# ELC102_-_Switch_Interface.net
KiCad netlist of a schematic drawn in Altium Designer
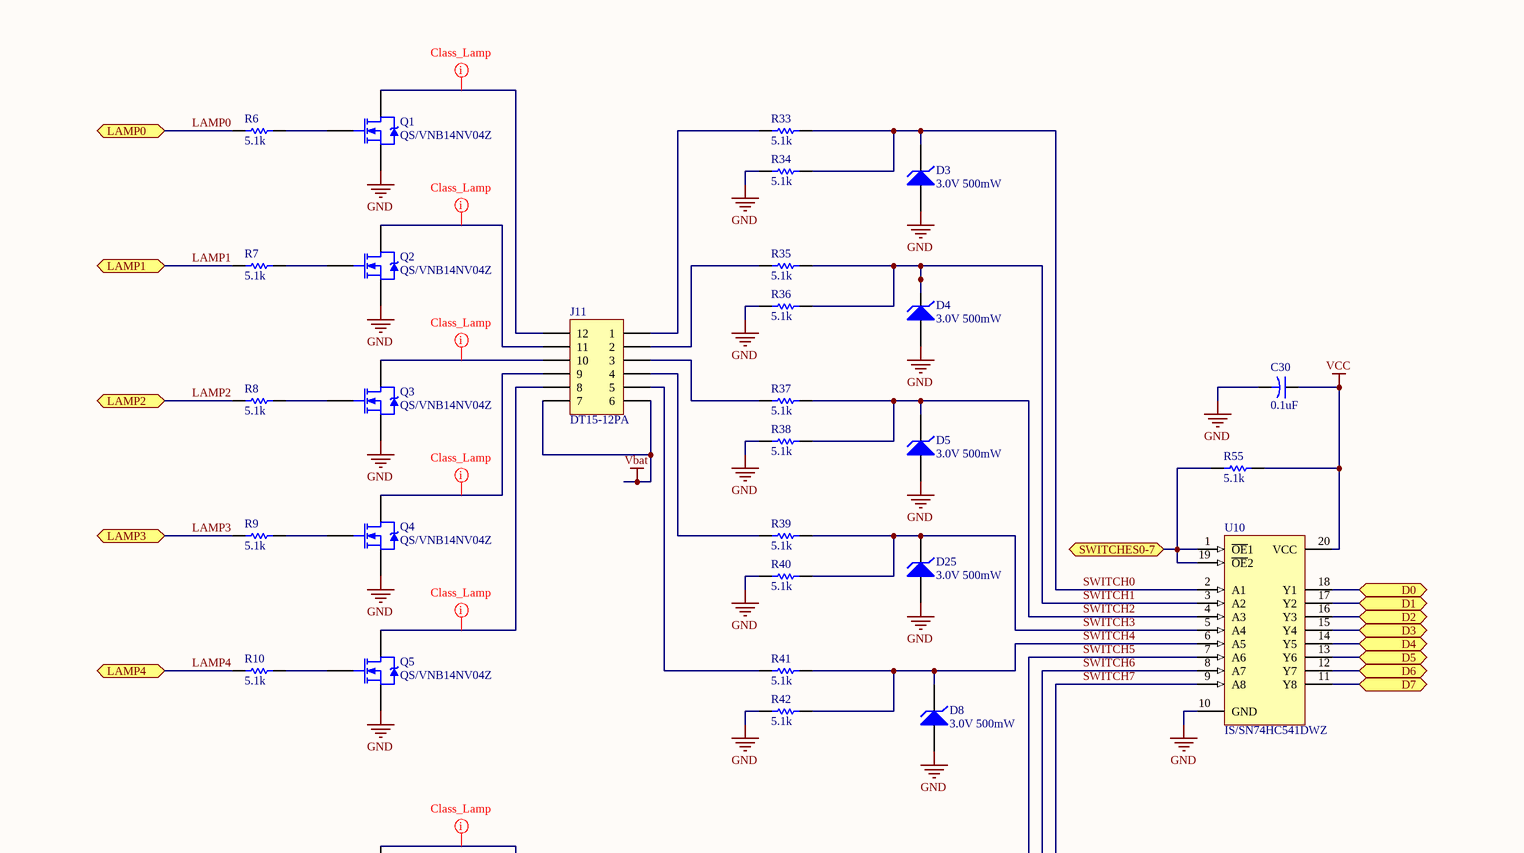
[diagram p0: ELC102 - Switch Interface.SchDoc, top left]
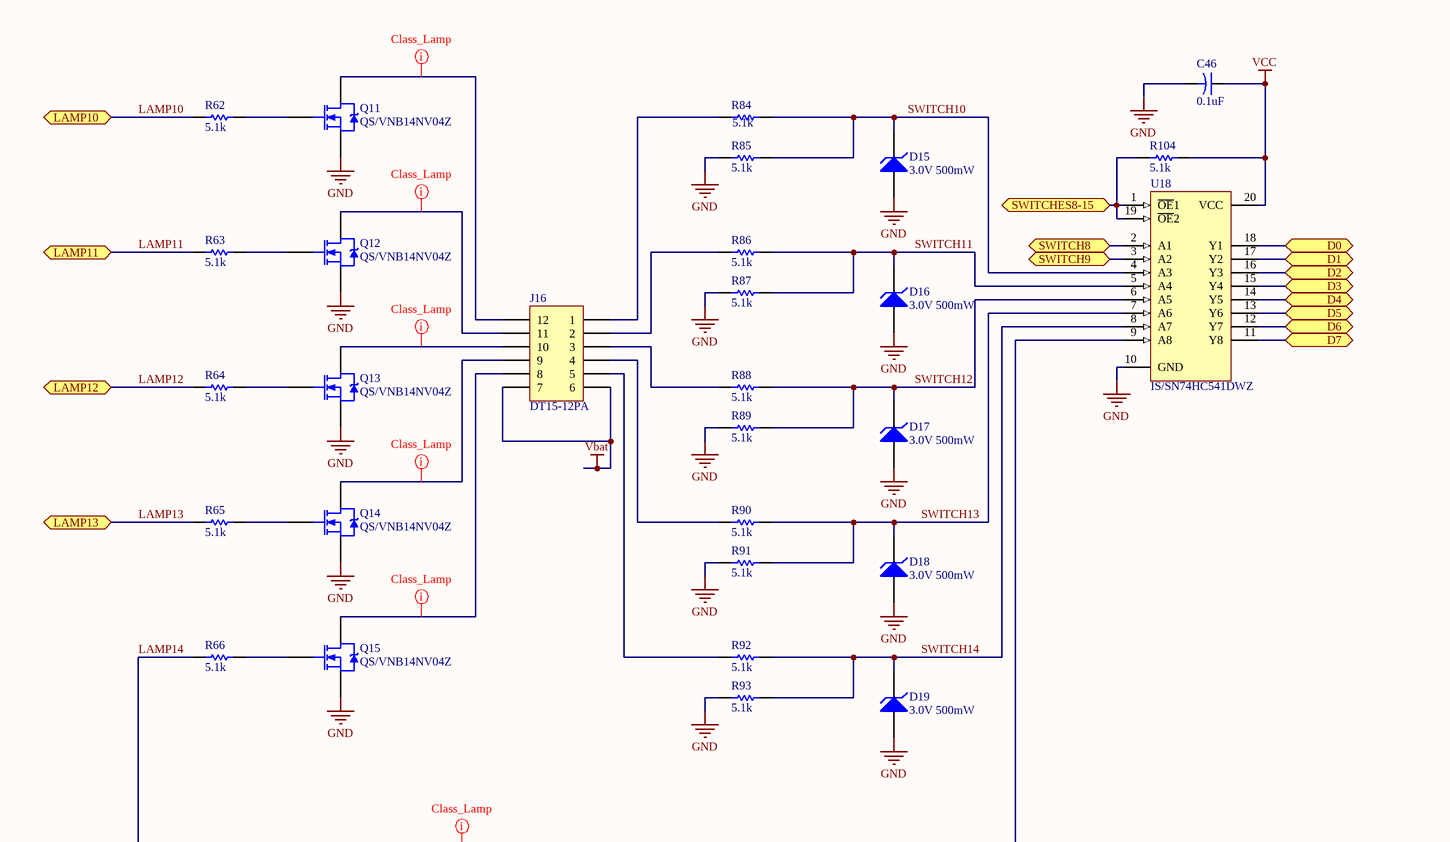
[diagram p1: ELC102 - Switch Interface.SchDoc, top right]
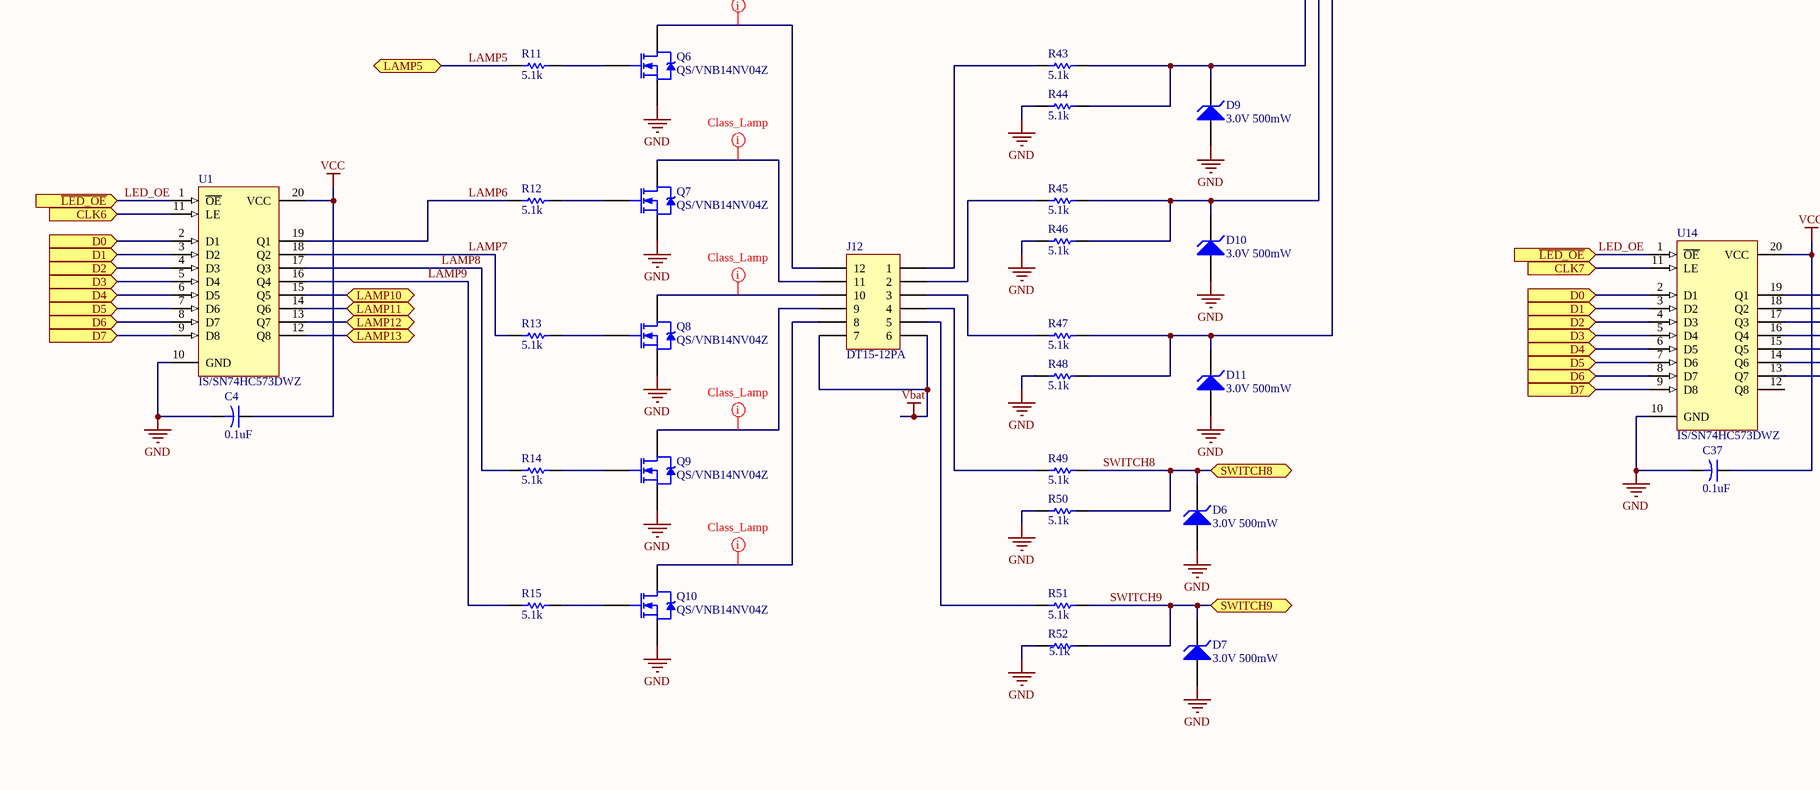
[diagram p2: ELC102 - Switch Interface.SchDoc, bottom left]
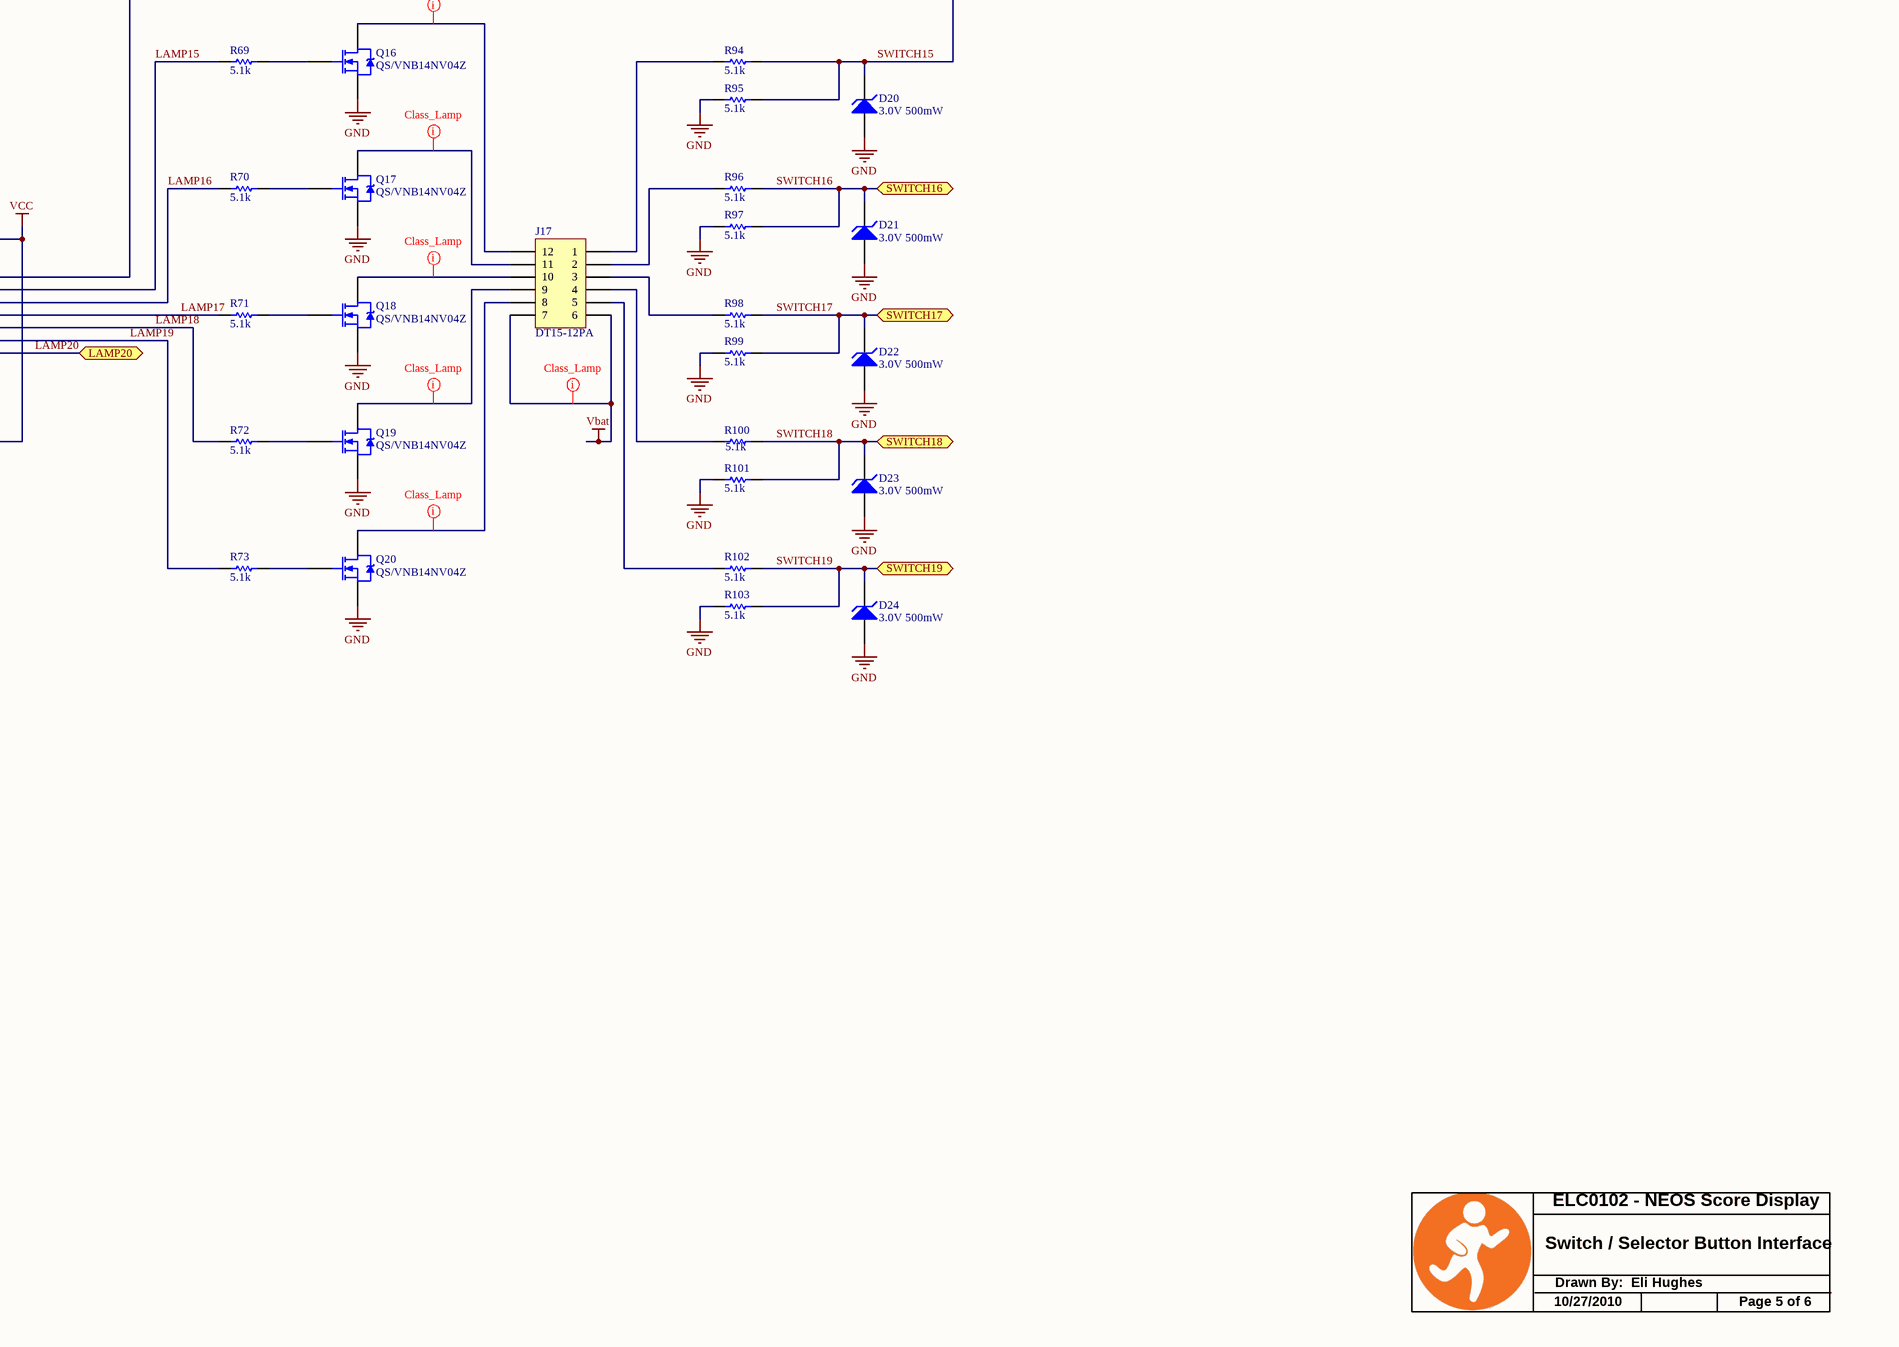
[diagram p3: ELC102 - Switch Interface.SchDoc, bottom right]

(export (version "E")
  (design (tool "Eeschema 10.0.6"))
  (components
    (comp (ref "C4")
      (value "0.1uF")
      (footprint "C0805")
      (description "Kemet .1uF 0805")
      (fields
        (field (name "MANUFACTURER") "Kemet")
        (field (name "MANUFACTURER PART NUMBER") "C0805C104K5RACTU")
        (field (name "SOURCE") "Digikey")
      )
      (libsource (lib "ScoreBoard") (part "CS/C0805C104K5RACK"))
    )
    (comp (ref "C30")
      (value "0.1uF")
      (footprint "C0805")
      (description "Kemet .1uF 0805")
      (fields
        (field (name "MANUFACTURER") "Kemet")
        (field (name "MANUFACTURER PART NUMBER") "C0805C104K5RACTU")
        (field (name "SOURCE") "Digikey")
      )
      (libsource (lib "ScoreBoard") (part "CS/C0805C104K5RACK"))
    )
    (comp (ref "C37")
      (value "0.1uF")
      (footprint "C0805")
      (description "Kemet .1uF 0805")
      (fields
        (field (name "MANUFACTURER") "Kemet")
        (field (name "MANUFACTURER PART NUMBER") "C0805C104K5RACTU")
        (field (name "SOURCE") "Digikey")
      )
      (libsource (lib "ScoreBoard") (part "CS/C0805C104K5RACK"))
    )
    (comp (ref "C46")
      (value "0.1uF")
      (footprint "C0805")
      (description "Kemet .1uF 0805")
      (fields
        (field (name "MANUFACTURER") "Kemet")
        (field (name "MANUFACTURER PART NUMBER") "C0805C104K5RACTU")
        (field (name "SOURCE") "Digikey")
      )
      (libsource (lib "ScoreBoard") (part "CS/C0805C104K5RACK"))
    )
    (comp (ref "D3")
      (value "3.0V 500mW")
      (footprint "SOD123")
      (description "Zener 3.0V SOD-123")
      (fields
        (field (name "MANUFACTURER") "ON Semiconductor")
        (field (name "MANUFACTURER PART NUMBER") "MMSZ5225BT1G")
        (field (name "SOURCE") "Digikey")
      )
      (libsource (lib "ScoreBoard") (part "DS/MMSZ5225BT1Z"))
    )
    (comp (ref "D4")
      (value "3.0V 500mW")
      (footprint "SOD123")
      (description "Zener 3.0V SOD-123")
      (fields
        (field (name "MANUFACTURER") "ON Semiconductor")
        (field (name "MANUFACTURER PART NUMBER") "MMSZ5225BT1G")
        (field (name "SOURCE") "Digikey")
      )
      (libsource (lib "ScoreBoard") (part "DS/MMSZ5225BT1Z"))
    )
    (comp (ref "D5")
      (value "3.0V 500mW")
      (footprint "SOD123")
      (description "Zener 3.0V SOD-123")
      (fields
        (field (name "MANUFACTURER") "ON Semiconductor")
        (field (name "MANUFACTURER PART NUMBER") "MMSZ5225BT1G")
        (field (name "SOURCE") "Digikey")
      )
      (libsource (lib "ScoreBoard") (part "DS/MMSZ5225BT1Z"))
    )
    (comp (ref "D6")
      (value "3.0V 500mW")
      (footprint "SOD123")
      (description "Zener 3.0V SOD-123")
      (fields
        (field (name "MANUFACTURER") "ON Semiconductor")
        (field (name "MANUFACTURER PART NUMBER") "MMSZ5225BT1G")
        (field (name "SOURCE") "Digikey")
      )
      (libsource (lib "ScoreBoard") (part "DS/MMSZ5225BT1Z"))
    )
    (comp (ref "D7")
      (value "3.0V 500mW")
      (footprint "SOD123")
      (description "Zener 3.0V SOD-123")
      (fields
        (field (name "MANUFACTURER") "ON Semiconductor")
        (field (name "MANUFACTURER PART NUMBER") "MMSZ5225BT1G")
        (field (name "SOURCE") "Digikey")
      )
      (libsource (lib "ScoreBoard") (part "DS/MMSZ5225BT1Z"))
    )
    (comp (ref "D8")
      (value "3.0V 500mW")
      (footprint "SOD123")
      (description "Zener 3.0V SOD-123")
      (fields
        (field (name "MANUFACTURER") "ON Semiconductor")
        (field (name "MANUFACTURER PART NUMBER") "MMSZ5225BT1G")
        (field (name "SOURCE") "Digikey")
      )
      (libsource (lib "ScoreBoard") (part "DS/MMSZ5225BT1Z"))
    )
    (comp (ref "D9")
      (value "3.0V 500mW")
      (footprint "SOD123")
      (description "Zener 3.0V SOD-123")
      (fields
        (field (name "MANUFACTURER") "ON Semiconductor")
        (field (name "MANUFACTURER PART NUMBER") "MMSZ5225BT1G")
        (field (name "SOURCE") "Digikey")
      )
      (libsource (lib "ScoreBoard") (part "DS/MMSZ5225BT1Z"))
    )
    (comp (ref "D10")
      (value "3.0V 500mW")
      (footprint "SOD123")
      (description "Zener 3.0V SOD-123")
      (fields
        (field (name "MANUFACTURER") "ON Semiconductor")
        (field (name "MANUFACTURER PART NUMBER") "MMSZ5225BT1G")
        (field (name "SOURCE") "Digikey")
      )
      (libsource (lib "ScoreBoard") (part "DS/MMSZ5225BT1Z"))
    )
    (comp (ref "D11")
      (value "3.0V 500mW")
      (footprint "SOD123")
      (description "Zener 3.0V SOD-123")
      (fields
        (field (name "MANUFACTURER") "ON Semiconductor")
        (field (name "MANUFACTURER PART NUMBER") "MMSZ5225BT1G")
        (field (name "SOURCE") "Digikey")
      )
      (libsource (lib "ScoreBoard") (part "DS/MMSZ5225BT1Z"))
    )
    (comp (ref "D15")
      (value "3.0V 500mW")
      (footprint "SOD123")
      (description "Zener 3.0V SOD-123")
      (fields
        (field (name "MANUFACTURER") "ON Semiconductor")
        (field (name "MANUFACTURER PART NUMBER") "MMSZ5225BT1G")
        (field (name "SOURCE") "Digikey")
      )
      (libsource (lib "ScoreBoard") (part "DS/MMSZ5225BT1Z"))
    )
    (comp (ref "D16")
      (value "3.0V 500mW")
      (footprint "SOD123")
      (description "Zener 3.0V SOD-123")
      (fields
        (field (name "MANUFACTURER") "ON Semiconductor")
        (field (name "MANUFACTURER PART NUMBER") "MMSZ5225BT1G")
        (field (name "SOURCE") "Digikey")
      )
      (libsource (lib "ScoreBoard") (part "DS/MMSZ5225BT1Z"))
    )
    (comp (ref "D17")
      (value "3.0V 500mW")
      (footprint "SOD123")
      (description "Zener 3.0V SOD-123")
      (fields
        (field (name "MANUFACTURER") "ON Semiconductor")
        (field (name "MANUFACTURER PART NUMBER") "MMSZ5225BT1G")
        (field (name "SOURCE") "Digikey")
      )
      (libsource (lib "ScoreBoard") (part "DS/MMSZ5225BT1Z"))
    )
    (comp (ref "D18")
      (value "3.0V 500mW")
      (footprint "SOD123")
      (description "Zener 3.0V SOD-123")
      (fields
        (field (name "MANUFACTURER") "ON Semiconductor")
        (field (name "MANUFACTURER PART NUMBER") "MMSZ5225BT1G")
        (field (name "SOURCE") "Digikey")
      )
      (libsource (lib "ScoreBoard") (part "DS/MMSZ5225BT1Z"))
    )
    (comp (ref "D19")
      (value "3.0V 500mW")
      (footprint "SOD123")
      (description "Zener 3.0V SOD-123")
      (fields
        (field (name "MANUFACTURER") "ON Semiconductor")
        (field (name "MANUFACTURER PART NUMBER") "MMSZ5225BT1G")
        (field (name "SOURCE") "Digikey")
      )
      (libsource (lib "ScoreBoard") (part "DS/MMSZ5225BT1Z"))
    )
    (comp (ref "D20")
      (value "3.0V 500mW")
      (footprint "SOD123")
      (description "Zener 3.0V SOD-123")
      (fields
        (field (name "MANUFACTURER") "ON Semiconductor")
        (field (name "MANUFACTURER PART NUMBER") "MMSZ5225BT1G")
        (field (name "SOURCE") "Digikey")
      )
      (libsource (lib "ScoreBoard") (part "DS/MMSZ5225BT1Z"))
    )
    (comp (ref "D21")
      (value "3.0V 500mW")
      (footprint "SOD123")
      (description "Zener 3.0V SOD-123")
      (fields
        (field (name "MANUFACTURER") "ON Semiconductor")
        (field (name "MANUFACTURER PART NUMBER") "MMSZ5225BT1G")
        (field (name "SOURCE") "Digikey")
      )
      (libsource (lib "ScoreBoard") (part "DS/MMSZ5225BT1Z"))
    )
    (comp (ref "D22")
      (value "3.0V 500mW")
      (footprint "SOD123")
      (description "Zener 3.0V SOD-123")
      (fields
        (field (name "MANUFACTURER") "ON Semiconductor")
        (field (name "MANUFACTURER PART NUMBER") "MMSZ5225BT1G")
        (field (name "SOURCE") "Digikey")
      )
      (libsource (lib "ScoreBoard") (part "DS/MMSZ5225BT1Z"))
    )
    (comp (ref "D23")
      (value "3.0V 500mW")
      (footprint "SOD123")
      (description "Zener 3.0V SOD-123")
      (fields
        (field (name "MANUFACTURER") "ON Semiconductor")
        (field (name "MANUFACTURER PART NUMBER") "MMSZ5225BT1G")
        (field (name "SOURCE") "Digikey")
      )
      (libsource (lib "ScoreBoard") (part "DS/MMSZ5225BT1Z"))
    )
    (comp (ref "D24")
      (value "3.0V 500mW")
      (footprint "SOD123")
      (description "Zener 3.0V SOD-123")
      (fields
        (field (name "MANUFACTURER") "ON Semiconductor")
        (field (name "MANUFACTURER PART NUMBER") "MMSZ5225BT1G")
        (field (name "SOURCE") "Digikey")
      )
      (libsource (lib "ScoreBoard") (part "DS/MMSZ5225BT1Z"))
    )
    (comp (ref "D25")
      (value "3.0V 500mW")
      (footprint "SOD123")
      (description "Zener 3.0V SOD-123")
      (fields
        (field (name "MANUFACTURER") "ON Semiconductor")
        (field (name "MANUFACTURER PART NUMBER") "MMSZ5225BT1G")
        (field (name "SOURCE") "Digikey")
      )
      (libsource (lib "ScoreBoard") (part "DS/MMSZ5225BT1Z"))
    )
    (comp (ref "J11")
      (value "DT15-12PA")
      (footprint "JDT1512PA00Z")
      (description "Deutsch 12P Sealed PCB connector")
      (fields (field (name "MANUFACTURER") "Deutsch"))
      (libsource (lib "ScoreBoard") (part "JDT1512PA00Z"))
    )
    (comp (ref "J12")
      (value "DT15-12PA")
      (footprint "JDT1512PA00Z")
      (description "Deutsch 12P Sealed PCB connector")
      (fields (field (name "MANUFACTURER") "Deutsch"))
      (libsource (lib "ScoreBoard") (part "JDT1512PA00Z"))
    )
    (comp (ref "J16")
      (value "DT15-12PA")
      (footprint "JDT1512PA00Z")
      (description "Deutsch 12P Sealed PCB connector")
      (fields (field (name "MANUFACTURER") "Deutsch"))
      (libsource (lib "ScoreBoard") (part "JDT1512PA00Z"))
    )
    (comp (ref "J17")
      (value "DT15-12PA")
      (footprint "JDT1512PA00Z")
      (description "Deutsch 12P Sealed PCB connector")
      (fields (field (name "MANUFACTURER") "Deutsch"))
      (libsource (lib "ScoreBoard") (part "JDT1512PA00Z"))
    )
    (comp (ref "Q1")
      (value "QS/VNB14NV04Z")
      (footprint "D2PAK")
      (description "HEXFET Power MOSFET")
      (fields
        (field (name "MANUFACTURER") "STMicroelectronics")
        (field (name "MANUFACTURER PART NUMBER") "VNB14NV04")
        (field (name "SOURCE") "Digikey")
      )
      (libsource (lib "ScoreBoard") (part "QS/VNB14NV04Z"))
    )
    (comp (ref "Q2")
      (value "QS/VNB14NV04Z")
      (footprint "D2PAK")
      (description "HEXFET Power MOSFET")
      (fields
        (field (name "MANUFACTURER") "STMicroelectronics")
        (field (name "MANUFACTURER PART NUMBER") "VNB14NV04")
        (field (name "SOURCE") "Digikey")
      )
      (libsource (lib "ScoreBoard") (part "QS/VNB14NV04Z"))
    )
    (comp (ref "Q3")
      (value "QS/VNB14NV04Z")
      (footprint "D2PAK")
      (description "HEXFET Power MOSFET")
      (fields
        (field (name "MANUFACTURER") "STMicroelectronics")
        (field (name "MANUFACTURER PART NUMBER") "VNB14NV04")
        (field (name "SOURCE") "Digikey")
      )
      (libsource (lib "ScoreBoard") (part "QS/VNB14NV04Z"))
    )
    (comp (ref "Q4")
      (value "QS/VNB14NV04Z")
      (footprint "D2PAK")
      (description "HEXFET Power MOSFET")
      (fields
        (field (name "MANUFACTURER") "STMicroelectronics")
        (field (name "MANUFACTURER PART NUMBER") "VNB14NV04")
        (field (name "SOURCE") "Digikey")
      )
      (libsource (lib "ScoreBoard") (part "QS/VNB14NV04Z"))
    )
    (comp (ref "Q5")
      (value "QS/VNB14NV04Z")
      (footprint "D2PAK")
      (description "HEXFET Power MOSFET")
      (fields
        (field (name "MANUFACTURER") "STMicroelectronics")
        (field (name "MANUFACTURER PART NUMBER") "VNB14NV04")
        (field (name "SOURCE") "Digikey")
      )
      (libsource (lib "ScoreBoard") (part "QS/VNB14NV04Z"))
    )
    (comp (ref "Q6")
      (value "QS/VNB14NV04Z")
      (footprint "D2PAK")
      (description "HEXFET Power MOSFET")
      (fields
        (field (name "MANUFACTURER") "STMicroelectronics")
        (field (name "MANUFACTURER PART NUMBER") "VNB14NV04")
        (field (name "SOURCE") "Digikey")
      )
      (libsource (lib "ScoreBoard") (part "QS/VNB14NV04Z"))
    )
    (comp (ref "Q7")
      (value "QS/VNB14NV04Z")
      (footprint "D2PAK")
      (description "HEXFET Power MOSFET")
      (fields
        (field (name "MANUFACTURER") "STMicroelectronics")
        (field (name "MANUFACTURER PART NUMBER") "VNB14NV04")
        (field (name "SOURCE") "Digikey")
      )
      (libsource (lib "ScoreBoard") (part "QS/VNB14NV04Z"))
    )
    (comp (ref "Q8")
      (value "QS/VNB14NV04Z")
      (footprint "D2PAK")
      (description "HEXFET Power MOSFET")
      (fields
        (field (name "MANUFACTURER") "STMicroelectronics")
        (field (name "MANUFACTURER PART NUMBER") "VNB14NV04")
        (field (name "SOURCE") "Digikey")
      )
      (libsource (lib "ScoreBoard") (part "QS/VNB14NV04Z"))
    )
    (comp (ref "Q9")
      (value "QS/VNB14NV04Z")
      (footprint "D2PAK")
      (description "HEXFET Power MOSFET")
      (fields
        (field (name "MANUFACTURER") "STMicroelectronics")
        (field (name "MANUFACTURER PART NUMBER") "VNB14NV04")
        (field (name "SOURCE") "Digikey")
      )
      (libsource (lib "ScoreBoard") (part "QS/VNB14NV04Z"))
    )
    (comp (ref "Q10")
      (value "QS/VNB14NV04Z")
      (footprint "D2PAK")
      (description "HEXFET Power MOSFET")
      (fields
        (field (name "MANUFACTURER") "STMicroelectronics")
        (field (name "MANUFACTURER PART NUMBER") "VNB14NV04")
        (field (name "SOURCE") "Digikey")
      )
      (libsource (lib "ScoreBoard") (part "QS/VNB14NV04Z"))
    )
    (comp (ref "Q11")
      (value "QS/VNB14NV04Z")
      (footprint "D2PAK")
      (description "HEXFET Power MOSFET")
      (fields
        (field (name "MANUFACTURER") "STMicroelectronics")
        (field (name "MANUFACTURER PART NUMBER") "VNB14NV04")
        (field (name "SOURCE") "Digikey")
      )
      (libsource (lib "ScoreBoard") (part "QS/VNB14NV04Z"))
    )
    (comp (ref "Q12")
      (value "QS/VNB14NV04Z")
      (footprint "D2PAK")
      (description "HEXFET Power MOSFET")
      (fields
        (field (name "MANUFACTURER") "STMicroelectronics")
        (field (name "MANUFACTURER PART NUMBER") "VNB14NV04")
        (field (name "SOURCE") "Digikey")
      )
      (libsource (lib "ScoreBoard") (part "QS/VNB14NV04Z"))
    )
    (comp (ref "Q13")
      (value "QS/VNB14NV04Z")
      (footprint "D2PAK")
      (description "HEXFET Power MOSFET")
      (fields
        (field (name "MANUFACTURER") "STMicroelectronics")
        (field (name "MANUFACTURER PART NUMBER") "VNB14NV04")
        (field (name "SOURCE") "Digikey")
      )
      (libsource (lib "ScoreBoard") (part "QS/VNB14NV04Z"))
    )
    (comp (ref "Q14")
      (value "QS/VNB14NV04Z")
      (footprint "D2PAK")
      (description "HEXFET Power MOSFET")
      (fields
        (field (name "MANUFACTURER") "STMicroelectronics")
        (field (name "MANUFACTURER PART NUMBER") "VNB14NV04")
        (field (name "SOURCE") "Digikey")
      )
      (libsource (lib "ScoreBoard") (part "QS/VNB14NV04Z"))
    )
    (comp (ref "Q15")
      (value "QS/VNB14NV04Z")
      (footprint "D2PAK")
      (description "HEXFET Power MOSFET")
      (fields
        (field (name "MANUFACTURER") "STMicroelectronics")
        (field (name "MANUFACTURER PART NUMBER") "VNB14NV04")
        (field (name "SOURCE") "Digikey")
      )
      (libsource (lib "ScoreBoard") (part "QS/VNB14NV04Z"))
    )
    (comp (ref "Q16")
      (value "QS/VNB14NV04Z")
      (footprint "D2PAK")
      (description "HEXFET Power MOSFET")
      (fields
        (field (name "MANUFACTURER") "STMicroelectronics")
        (field (name "MANUFACTURER PART NUMBER") "VNB14NV04")
        (field (name "SOURCE") "Digikey")
      )
      (libsource (lib "ScoreBoard") (part "QS/VNB14NV04Z"))
    )
    (comp (ref "Q17")
      (value "QS/VNB14NV04Z")
      (footprint "D2PAK")
      (description "HEXFET Power MOSFET")
      (fields
        (field (name "MANUFACTURER") "STMicroelectronics")
        (field (name "MANUFACTURER PART NUMBER") "VNB14NV04")
        (field (name "SOURCE") "Digikey")
      )
      (libsource (lib "ScoreBoard") (part "QS/VNB14NV04Z"))
    )
    (comp (ref "Q18")
      (value "QS/VNB14NV04Z")
      (footprint "D2PAK")
      (description "HEXFET Power MOSFET")
      (fields
        (field (name "MANUFACTURER") "STMicroelectronics")
        (field (name "MANUFACTURER PART NUMBER") "VNB14NV04")
        (field (name "SOURCE") "Digikey")
      )
      (libsource (lib "ScoreBoard") (part "QS/VNB14NV04Z"))
    )
    (comp (ref "Q19")
      (value "QS/VNB14NV04Z")
      (footprint "D2PAK")
      (description "HEXFET Power MOSFET")
      (fields
        (field (name "MANUFACTURER") "STMicroelectronics")
        (field (name "MANUFACTURER PART NUMBER") "VNB14NV04")
        (field (name "SOURCE") "Digikey")
      )
      (libsource (lib "ScoreBoard") (part "QS/VNB14NV04Z"))
    )
    (comp (ref "Q20")
      (value "QS/VNB14NV04Z")
      (footprint "D2PAK")
      (description "HEXFET Power MOSFET")
      (fields
        (field (name "MANUFACTURER") "STMicroelectronics")
        (field (name "MANUFACTURER PART NUMBER") "VNB14NV04")
        (field (name "SOURCE") "Digikey")
      )
      (libsource (lib "ScoreBoard") (part "QS/VNB14NV04Z"))
    )
    (comp (ref "R6")
      (value "5.1k")
      (footprint "R0805")
      (description "RES 5.10K OHM 1/8W 1% 0805 SMD")
      (fields
        (field (name "MANUFACTURER") "Panasonic - ECG")
        (field (name "MANUFACTURER PART NUMBER") "ERJ-6ENF5101V")
      )
      (libsource (lib "eRCL") (part "ERJ-6ENF5101V"))
    )
    (comp (ref "R7")
      (value "5.1k")
      (footprint "R0805")
      (description "RES 5.10K OHM 1/8W 1% 0805 SMD")
      (fields
        (field (name "MANUFACTURER") "Panasonic - ECG")
        (field (name "MANUFACTURER PART NUMBER") "ERJ-6ENF5101V")
      )
      (libsource (lib "eRCL") (part "ERJ-6ENF5101V"))
    )
    (comp (ref "R8")
      (value "5.1k")
      (footprint "R0805")
      (description "RES 5.10K OHM 1/8W 1% 0805 SMD")
      (fields
        (field (name "MANUFACTURER") "Panasonic - ECG")
        (field (name "MANUFACTURER PART NUMBER") "ERJ-6ENF5101V")
      )
      (libsource (lib "eRCL") (part "ERJ-6ENF5101V"))
    )
    (comp (ref "R9")
      (value "5.1k")
      (footprint "R0805")
      (description "RES 5.10K OHM 1/8W 1% 0805 SMD")
      (fields
        (field (name "MANUFACTURER") "Panasonic - ECG")
        (field (name "MANUFACTURER PART NUMBER") "ERJ-6ENF5101V")
      )
      (libsource (lib "eRCL") (part "ERJ-6ENF5101V"))
    )
    (comp (ref "R10")
      (value "5.1k")
      (footprint "R0805")
      (description "RES 5.10K OHM 1/8W 1% 0805 SMD")
      (fields
        (field (name "MANUFACTURER") "Panasonic - ECG")
        (field (name "MANUFACTURER PART NUMBER") "ERJ-6ENF5101V")
      )
      (libsource (lib "eRCL") (part "ERJ-6ENF5101V"))
    )
    (comp (ref "R11")
      (value "5.1k")
      (footprint "R0805")
      (description "RES 5.10K OHM 1/8W 1% 0805 SMD")
      (fields
        (field (name "MANUFACTURER") "Panasonic - ECG")
        (field (name "MANUFACTURER PART NUMBER") "ERJ-6ENF5101V")
      )
      (libsource (lib "eRCL") (part "ERJ-6ENF5101V"))
    )
    (comp (ref "R12")
      (value "5.1k")
      (footprint "R0805")
      (description "RES 5.10K OHM 1/8W 1% 0805 SMD")
      (fields
        (field (name "MANUFACTURER") "Panasonic - ECG")
        (field (name "MANUFACTURER PART NUMBER") "ERJ-6ENF5101V")
      )
      (libsource (lib "eRCL") (part "ERJ-6ENF5101V"))
    )
    (comp (ref "R13")
      (value "5.1k")
      (footprint "R0805")
      (description "RES 5.10K OHM 1/8W 1% 0805 SMD")
      (fields
        (field (name "MANUFACTURER") "Panasonic - ECG")
        (field (name "MANUFACTURER PART NUMBER") "ERJ-6ENF5101V")
      )
      (libsource (lib "eRCL") (part "ERJ-6ENF5101V"))
    )
    (comp (ref "R14")
      (value "5.1k")
      (footprint "R0805")
      (description "RES 5.10K OHM 1/8W 1% 0805 SMD")
      (fields
        (field (name "MANUFACTURER") "Panasonic - ECG")
        (field (name "MANUFACTURER PART NUMBER") "ERJ-6ENF5101V")
      )
      (libsource (lib "eRCL") (part "ERJ-6ENF5101V"))
    )
    (comp (ref "R15")
      (value "5.1k")
      (footprint "R0805")
      (description "RES 5.10K OHM 1/8W 1% 0805 SMD")
      (fields
        (field (name "MANUFACTURER") "Panasonic - ECG")
        (field (name "MANUFACTURER PART NUMBER") "ERJ-6ENF5101V")
      )
      (libsource (lib "eRCL") (part "ERJ-6ENF5101V"))
    )
    (comp (ref "R33")
      (value "5.1k")
      (footprint "R0805")
      (description "RES 5.10K OHM 1/8W 1% 0805 SMD")
      (fields
        (field (name "MANUFACTURER") "Panasonic - ECG")
        (field (name "MANUFACTURER PART NUMBER") "ERJ-6ENF5101V")
      )
      (libsource (lib "eRCL") (part "ERJ-6ENF5101V"))
    )
    (comp (ref "R34")
      (value "5.1k")
      (footprint "R0805")
      (description "RES 5.10K OHM 1/8W 1% 0805 SMD")
      (fields
        (field (name "MANUFACTURER") "Panasonic - ECG")
        (field (name "MANUFACTURER PART NUMBER") "ERJ-6ENF5101V")
      )
      (libsource (lib "eRCL") (part "ERJ-6ENF5101V"))
    )
    (comp (ref "R35")
      (value "5.1k")
      (footprint "R0805")
      (description "RES 5.10K OHM 1/8W 1% 0805 SMD")
      (fields
        (field (name "MANUFACTURER") "Panasonic - ECG")
        (field (name "MANUFACTURER PART NUMBER") "ERJ-6ENF5101V")
      )
      (libsource (lib "eRCL") (part "ERJ-6ENF5101V"))
    )
    (comp (ref "R36")
      (value "5.1k")
      (footprint "R0805")
      (description "RES 5.10K OHM 1/8W 1% 0805 SMD")
      (fields
        (field (name "MANUFACTURER") "Panasonic - ECG")
        (field (name "MANUFACTURER PART NUMBER") "ERJ-6ENF5101V")
      )
      (libsource (lib "eRCL") (part "ERJ-6ENF5101V"))
    )
    (comp (ref "R37")
      (value "5.1k")
      (footprint "R0805")
      (description "RES 5.10K OHM 1/8W 1% 0805 SMD")
      (fields
        (field (name "MANUFACTURER") "Panasonic - ECG")
        (field (name "MANUFACTURER PART NUMBER") "ERJ-6ENF5101V")
      )
      (libsource (lib "eRCL") (part "ERJ-6ENF5101V"))
    )
    (comp (ref "R38")
      (value "5.1k")
      (footprint "R0805")
      (description "RES 5.10K OHM 1/8W 1% 0805 SMD")
      (fields
        (field (name "MANUFACTURER") "Panasonic - ECG")
        (field (name "MANUFACTURER PART NUMBER") "ERJ-6ENF5101V")
      )
      (libsource (lib "eRCL") (part "ERJ-6ENF5101V"))
    )
    (comp (ref "R39")
      (value "5.1k")
      (footprint "R0805")
      (description "RES 5.10K OHM 1/8W 1% 0805 SMD")
      (fields
        (field (name "MANUFACTURER") "Panasonic - ECG")
        (field (name "MANUFACTURER PART NUMBER") "ERJ-6ENF5101V")
      )
      (libsource (lib "eRCL") (part "ERJ-6ENF5101V"))
    )
    (comp (ref "R40")
      (value "5.1k")
      (footprint "R0805")
      (description "RES 5.10K OHM 1/8W 1% 0805 SMD")
      (fields
        (field (name "MANUFACTURER") "Panasonic - ECG")
        (field (name "MANUFACTURER PART NUMBER") "ERJ-6ENF5101V")
      )
      (libsource (lib "eRCL") (part "ERJ-6ENF5101V"))
    )
    (comp (ref "R41")
      (value "5.1k")
      (footprint "R0805")
      (description "RES 5.10K OHM 1/8W 1% 0805 SMD")
      (fields
        (field (name "MANUFACTURER") "Panasonic - ECG")
        (field (name "MANUFACTURER PART NUMBER") "ERJ-6ENF5101V")
      )
      (libsource (lib "eRCL") (part "ERJ-6ENF5101V"))
    )
    (comp (ref "R42")
      (value "5.1k")
      (footprint "R0805")
      (description "RES 5.10K OHM 1/8W 1% 0805 SMD")
      (fields
        (field (name "MANUFACTURER") "Panasonic - ECG")
        (field (name "MANUFACTURER PART NUMBER") "ERJ-6ENF5101V")
      )
      (libsource (lib "eRCL") (part "ERJ-6ENF5101V"))
    )
    (comp (ref "R43")
      (value "5.1k")
      (footprint "R0805")
      (description "RES 5.10K OHM 1/8W 1% 0805 SMD")
      (fields
        (field (name "MANUFACTURER") "Panasonic - ECG")
        (field (name "MANUFACTURER PART NUMBER") "ERJ-6ENF5101V")
      )
      (libsource (lib "eRCL") (part "ERJ-6ENF5101V"))
    )
    (comp (ref "R44")
      (value "5.1k")
      (footprint "R0805")
      (description "RES 5.10K OHM 1/8W 1% 0805 SMD")
      (fields
        (field (name "MANUFACTURER") "Panasonic - ECG")
        (field (name "MANUFACTURER PART NUMBER") "ERJ-6ENF5101V")
      )
      (libsource (lib "eRCL") (part "ERJ-6ENF5101V"))
    )
    (comp (ref "R45")
      (value "5.1k")
      (footprint "R0805")
      (description "RES 5.10K OHM 1/8W 1% 0805 SMD")
      (fields
        (field (name "MANUFACTURER") "Panasonic - ECG")
        (field (name "MANUFACTURER PART NUMBER") "ERJ-6ENF5101V")
      )
      (libsource (lib "eRCL") (part "ERJ-6ENF5101V"))
    )
    (comp (ref "R46")
      (value "5.1k")
      (footprint "R0805")
      (description "RES 5.10K OHM 1/8W 1% 0805 SMD")
      (fields
        (field (name "MANUFACTURER") "Panasonic - ECG")
        (field (name "MANUFACTURER PART NUMBER") "ERJ-6ENF5101V")
      )
      (libsource (lib "eRCL") (part "ERJ-6ENF5101V"))
    )
    (comp (ref "R47")
      (value "5.1k")
      (footprint "R0805")
      (description "RES 5.10K OHM 1/8W 1% 0805 SMD")
      (fields
        (field (name "MANUFACTURER") "Panasonic - ECG")
        (field (name "MANUFACTURER PART NUMBER") "ERJ-6ENF5101V")
      )
      (libsource (lib "eRCL") (part "ERJ-6ENF5101V"))
    )
    (comp (ref "R48")
      (value "5.1k")
      (footprint "R0805")
      (description "RES 5.10K OHM 1/8W 1% 0805 SMD")
      (fields
        (field (name "MANUFACTURER") "Panasonic - ECG")
        (field (name "MANUFACTURER PART NUMBER") "ERJ-6ENF5101V")
      )
      (libsource (lib "eRCL") (part "ERJ-6ENF5101V"))
    )
    (comp (ref "R49")
      (value "5.1k")
      (footprint "R0805")
      (description "RES 5.10K OHM 1/8W 1% 0805 SMD")
      (fields
        (field (name "MANUFACTURER") "Panasonic - ECG")
        (field (name "MANUFACTURER PART NUMBER") "ERJ-6ENF5101V")
      )
      (libsource (lib "eRCL") (part "ERJ-6ENF5101V"))
    )
    (comp (ref "R50")
      (value "5.1k")
      (footprint "R0805")
      (description "RES 5.10K OHM 1/8W 1% 0805 SMD")
      (fields
        (field (name "MANUFACTURER") "Panasonic - ECG")
        (field (name "MANUFACTURER PART NUMBER") "ERJ-6ENF5101V")
      )
      (libsource (lib "eRCL") (part "ERJ-6ENF5101V"))
    )
    (comp (ref "R51")
      (value "5.1k")
      (footprint "R0805")
      (description "RES 5.10K OHM 1/8W 1% 0805 SMD")
      (fields
        (field (name "MANUFACTURER") "Panasonic - ECG")
        (field (name "MANUFACTURER PART NUMBER") "ERJ-6ENF5101V")
      )
      (libsource (lib "eRCL") (part "ERJ-6ENF5101V"))
    )
    (comp (ref "R52")
      (value "5.1k")
      (footprint "R0805")
      (description "RES 5.10K OHM 1/8W 1% 0805 SMD")
      (fields
        (field (name "MANUFACTURER") "Panasonic - ECG")
        (field (name "MANUFACTURER PART NUMBER") "ERJ-6ENF5101V")
      )
      (libsource (lib "eRCL") (part "ERJ-6ENF5101V"))
    )
    (comp (ref "R55")
      (value "5.1k")
      (footprint "R0805")
      (description "RES 5.10K OHM 1/8W 1% 0805 SMD")
      (fields
        (field (name "MANUFACTURER") "Panasonic - ECG")
        (field (name "MANUFACTURER PART NUMBER") "ERJ-6ENF5101V")
      )
      (libsource (lib "eRCL") (part "ERJ-6ENF5101V"))
    )
    (comp (ref "R62")
      (value "5.1k")
      (footprint "R0805")
      (description "RES 5.10K OHM 1/8W 1% 0805 SMD")
      (fields
        (field (name "MANUFACTURER") "Panasonic - ECG")
        (field (name "MANUFACTURER PART NUMBER") "ERJ-6ENF5101V")
      )
      (libsource (lib "eRCL") (part "ERJ-6ENF5101V"))
    )
    (comp (ref "R63")
      (value "5.1k")
      (footprint "R0805")
      (description "RES 5.10K OHM 1/8W 1% 0805 SMD")
      (fields
        (field (name "MANUFACTURER") "Panasonic - ECG")
        (field (name "MANUFACTURER PART NUMBER") "ERJ-6ENF5101V")
      )
      (libsource (lib "eRCL") (part "ERJ-6ENF5101V"))
    )
    (comp (ref "R64")
      (value "5.1k")
      (footprint "R0805")
      (description "RES 5.10K OHM 1/8W 1% 0805 SMD")
      (fields
        (field (name "MANUFACTURER") "Panasonic - ECG")
        (field (name "MANUFACTURER PART NUMBER") "ERJ-6ENF5101V")
      )
      (libsource (lib "eRCL") (part "ERJ-6ENF5101V"))
    )
    (comp (ref "R65")
      (value "5.1k")
      (footprint "R0805")
      (description "RES 5.10K OHM 1/8W 1% 0805 SMD")
      (fields
        (field (name "MANUFACTURER") "Panasonic - ECG")
        (field (name "MANUFACTURER PART NUMBER") "ERJ-6ENF5101V")
      )
      (libsource (lib "eRCL") (part "ERJ-6ENF5101V"))
    )
    (comp (ref "R66")
      (value "5.1k")
      (footprint "R0805")
      (description "RES 5.10K OHM 1/8W 1% 0805 SMD")
      (fields
        (field (name "MANUFACTURER") "Panasonic - ECG")
        (field (name "MANUFACTURER PART NUMBER") "ERJ-6ENF5101V")
      )
      (libsource (lib "eRCL") (part "ERJ-6ENF5101V"))
    )
    (comp (ref "R69")
      (value "5.1k")
      (footprint "R0805")
      (description "RES 5.10K OHM 1/8W 1% 0805 SMD")
      (fields
        (field (name "MANUFACTURER") "Panasonic - ECG")
        (field (name "MANUFACTURER PART NUMBER") "ERJ-6ENF5101V")
      )
      (libsource (lib "eRCL") (part "ERJ-6ENF5101V"))
    )
    (comp (ref "R70")
      (value "5.1k")
      (footprint "R0805")
      (description "RES 5.10K OHM 1/8W 1% 0805 SMD")
      (fields
        (field (name "MANUFACTURER") "Panasonic - ECG")
        (field (name "MANUFACTURER PART NUMBER") "ERJ-6ENF5101V")
      )
      (libsource (lib "eRCL") (part "ERJ-6ENF5101V"))
    )
    (comp (ref "R71")
      (value "5.1k")
      (footprint "R0805")
      (description "RES 5.10K OHM 1/8W 1% 0805 SMD")
      (fields
        (field (name "MANUFACTURER") "Panasonic - ECG")
        (field (name "MANUFACTURER PART NUMBER") "ERJ-6ENF5101V")
      )
      (libsource (lib "eRCL") (part "ERJ-6ENF5101V"))
    )
    (comp (ref "R72")
      (value "5.1k")
      (footprint "R0805")
      (description "RES 5.10K OHM 1/8W 1% 0805 SMD")
      (fields
        (field (name "MANUFACTURER") "Panasonic - ECG")
        (field (name "MANUFACTURER PART NUMBER") "ERJ-6ENF5101V")
      )
      (libsource (lib "eRCL") (part "ERJ-6ENF5101V"))
    )
    (comp (ref "R73")
      (value "5.1k")
      (footprint "R0805")
      (description "RES 5.10K OHM 1/8W 1% 0805 SMD")
      (fields
        (field (name "MANUFACTURER") "Panasonic - ECG")
        (field (name "MANUFACTURER PART NUMBER") "ERJ-6ENF5101V")
      )
      (libsource (lib "eRCL") (part "ERJ-6ENF5101V"))
    )
    (comp (ref "R84")
      (value "5.1k")
      (footprint "R0805")
      (description "RES 5.10K OHM 1/8W 1% 0805 SMD")
      (fields
        (field (name "MANUFACTURER") "Panasonic - ECG")
        (field (name "MANUFACTURER PART NUMBER") "ERJ-6ENF5101V")
      )
      (libsource (lib "eRCL") (part "ERJ-6ENF5101V"))
    )
    (comp (ref "R85")
      (value "5.1k")
      (footprint "R0805")
      (description "RES 5.10K OHM 1/8W 1% 0805 SMD")
      (fields
        (field (name "MANUFACTURER") "Panasonic - ECG")
        (field (name "MANUFACTURER PART NUMBER") "ERJ-6ENF5101V")
      )
      (libsource (lib "eRCL") (part "ERJ-6ENF5101V"))
    )
    (comp (ref "R86")
      (value "5.1k")
      (footprint "R0805")
      (description "RES 5.10K OHM 1/8W 1% 0805 SMD")
      (fields
        (field (name "MANUFACTURER") "Panasonic - ECG")
        (field (name "MANUFACTURER PART NUMBER") "ERJ-6ENF5101V")
      )
      (libsource (lib "eRCL") (part "ERJ-6ENF5101V"))
    )
    (comp (ref "R87")
      (value "5.1k")
      (footprint "R0805")
      (description "RES 5.10K OHM 1/8W 1% 0805 SMD")
      (fields
        (field (name "MANUFACTURER") "Panasonic - ECG")
        (field (name "MANUFACTURER PART NUMBER") "ERJ-6ENF5101V")
      )
      (libsource (lib "eRCL") (part "ERJ-6ENF5101V"))
    )
    (comp (ref "R88")
      (value "5.1k")
      (footprint "R0805")
      (description "RES 5.10K OHM 1/8W 1% 0805 SMD")
      (fields
        (field (name "MANUFACTURER") "Panasonic - ECG")
        (field (name "MANUFACTURER PART NUMBER") "ERJ-6ENF5101V")
      )
      (libsource (lib "eRCL") (part "ERJ-6ENF5101V"))
    )
    (comp (ref "R89")
      (value "5.1k")
      (footprint "R0805")
      (description "RES 5.10K OHM 1/8W 1% 0805 SMD")
      (fields
        (field (name "MANUFACTURER") "Panasonic - ECG")
        (field (name "MANUFACTURER PART NUMBER") "ERJ-6ENF5101V")
      )
      (libsource (lib "eRCL") (part "ERJ-6ENF5101V"))
    )
    (comp (ref "R90")
      (value "5.1k")
      (footprint "R0805")
      (description "RES 5.10K OHM 1/8W 1% 0805 SMD")
      (fields
        (field (name "MANUFACTURER") "Panasonic - ECG")
        (field (name "MANUFACTURER PART NUMBER") "ERJ-6ENF5101V")
      )
      (libsource (lib "eRCL") (part "ERJ-6ENF5101V"))
    )
    (comp (ref "R91")
      (value "5.1k")
      (footprint "R0805")
      (description "RES 5.10K OHM 1/8W 1% 0805 SMD")
      (fields
        (field (name "MANUFACTURER") "Panasonic - ECG")
        (field (name "MANUFACTURER PART NUMBER") "ERJ-6ENF5101V")
      )
      (libsource (lib "eRCL") (part "ERJ-6ENF5101V"))
    )
    (comp (ref "R92")
      (value "5.1k")
      (footprint "R0805")
      (description "RES 5.10K OHM 1/8W 1% 0805 SMD")
      (fields
        (field (name "MANUFACTURER") "Panasonic - ECG")
        (field (name "MANUFACTURER PART NUMBER") "ERJ-6ENF5101V")
      )
      (libsource (lib "eRCL") (part "ERJ-6ENF5101V"))
    )
    (comp (ref "R93")
      (value "5.1k")
      (footprint "R0805")
      (description "RES 5.10K OHM 1/8W 1% 0805 SMD")
      (fields
        (field (name "MANUFACTURER") "Panasonic - ECG")
        (field (name "MANUFACTURER PART NUMBER") "ERJ-6ENF5101V")
      )
      (libsource (lib "eRCL") (part "ERJ-6ENF5101V"))
    )
    (comp (ref "R94")
      (value "5.1k")
      (footprint "R0805")
      (description "RES 5.10K OHM 1/8W 1% 0805 SMD")
      (fields
        (field (name "MANUFACTURER") "Panasonic - ECG")
        (field (name "MANUFACTURER PART NUMBER") "ERJ-6ENF5101V")
      )
      (libsource (lib "eRCL") (part "ERJ-6ENF5101V"))
    )
    (comp (ref "R95")
      (value "5.1k")
      (footprint "R0805")
      (description "RES 5.10K OHM 1/8W 1% 0805 SMD")
      (fields
        (field (name "MANUFACTURER") "Panasonic - ECG")
        (field (name "MANUFACTURER PART NUMBER") "ERJ-6ENF5101V")
      )
      (libsource (lib "eRCL") (part "ERJ-6ENF5101V"))
    )
    (comp (ref "R96")
      (value "5.1k")
      (footprint "R0805")
      (description "RES 5.10K OHM 1/8W 1% 0805 SMD")
      (fields
        (field (name "MANUFACTURER") "Panasonic - ECG")
        (field (name "MANUFACTURER PART NUMBER") "ERJ-6ENF5101V")
      )
      (libsource (lib "eRCL") (part "ERJ-6ENF5101V"))
    )
    (comp (ref "R97")
      (value "5.1k")
      (footprint "R0805")
      (description "RES 5.10K OHM 1/8W 1% 0805 SMD")
      (fields
        (field (name "MANUFACTURER") "Panasonic - ECG")
        (field (name "MANUFACTURER PART NUMBER") "ERJ-6ENF5101V")
      )
      (libsource (lib "eRCL") (part "ERJ-6ENF5101V"))
    )
    (comp (ref "R98")
      (value "5.1k")
      (footprint "R0805")
      (description "RES 5.10K OHM 1/8W 1% 0805 SMD")
      (fields
        (field (name "MANUFACTURER") "Panasonic - ECG")
        (field (name "MANUFACTURER PART NUMBER") "ERJ-6ENF5101V")
      )
      (libsource (lib "eRCL") (part "ERJ-6ENF5101V"))
    )
    (comp (ref "R99")
      (value "5.1k")
      (footprint "R0805")
      (description "RES 5.10K OHM 1/8W 1% 0805 SMD")
      (fields
        (field (name "MANUFACTURER") "Panasonic - ECG")
        (field (name "MANUFACTURER PART NUMBER") "ERJ-6ENF5101V")
      )
      (libsource (lib "eRCL") (part "ERJ-6ENF5101V"))
    )
    (comp (ref "R100")
      (value "5.1k")
      (footprint "R0805")
      (description "RES 5.10K OHM 1/8W 1% 0805 SMD")
      (fields
        (field (name "MANUFACTURER") "Panasonic - ECG")
        (field (name "MANUFACTURER PART NUMBER") "ERJ-6ENF5101V")
      )
      (libsource (lib "eRCL") (part "ERJ-6ENF5101V"))
    )
    (comp (ref "R101")
      (value "5.1k")
      (footprint "R0805")
      (description "RES 5.10K OHM 1/8W 1% 0805 SMD")
      (fields
        (field (name "MANUFACTURER") "Panasonic - ECG")
        (field (name "MANUFACTURER PART NUMBER") "ERJ-6ENF5101V")
      )
      (libsource (lib "eRCL") (part "ERJ-6ENF5101V"))
    )
    (comp (ref "R102")
      (value "5.1k")
      (footprint "R0805")
      (description "RES 5.10K OHM 1/8W 1% 0805 SMD")
      (fields
        (field (name "MANUFACTURER") "Panasonic - ECG")
        (field (name "MANUFACTURER PART NUMBER") "ERJ-6ENF5101V")
      )
      (libsource (lib "eRCL") (part "ERJ-6ENF5101V"))
    )
    (comp (ref "R103")
      (value "5.1k")
      (footprint "R0805")
      (description "RES 5.10K OHM 1/8W 1% 0805 SMD")
      (fields
        (field (name "MANUFACTURER") "Panasonic - ECG")
        (field (name "MANUFACTURER PART NUMBER") "ERJ-6ENF5101V")
      )
      (libsource (lib "eRCL") (part "ERJ-6ENF5101V"))
    )
    (comp (ref "R104")
      (value "5.1k")
      (footprint "R0805")
      (description "RES 5.10K OHM 1/8W 1% 0805 SMD")
      (fields
        (field (name "MANUFACTURER") "Panasonic - ECG")
        (field (name "MANUFACTURER PART NUMBER") "ERJ-6ENF5101V")
      )
      (libsource (lib "eRCL") (part "ERJ-6ENF5101V"))
    )
    (comp (ref "U1")
      (value "IS/SN74HC573DWZ")
      (footprint "SOIC300-20")
      (description "Octal D-Type Transparent Latch with 3-State Outputs")
      (fields
        (field (name "MANUFACTURER") "NXP Semiconductors")
        (field (name "MANUFACTURER PART NUMBER") "74HC573D-T")
        (field (name "SOURCE") "Digikey")
      )
      (libsource (lib "ScoreBoard") (part "IS/SN74HC573DWZ"))
    )
    (comp (ref "U10")
      (value "IS/SN74HC541DWZ")
      (footprint "SOIC300-20")
      (description "Octal Buffer and Line Driver with 3-State Outputs")
      (fields
        (field (name "MANUFACTURER") "Texas Instruments")
        (field (name "MANUFACTURER PART NUMBER") "SN74HC541DWR")
        (field (name "SOURCE") "Digikey")
      )
      (libsource (lib "ScoreBoard") (part "IS/SN74HC541DWZ"))
    )
    (comp (ref "U14")
      (value "IS/SN74HC573DWZ")
      (footprint "SOIC300-20")
      (description "Octal D-Type Transparent Latch with 3-State Outputs")
      (fields
        (field (name "MANUFACTURER") "NXP Semiconductors")
        (field (name "MANUFACTURER PART NUMBER") "74HC573D-T")
        (field (name "SOURCE") "Digikey")
      )
      (libsource (lib "ScoreBoard") (part "IS/SN74HC573DWZ"))
    )
    (comp (ref "U18")
      (value "IS/SN74HC541DWZ")
      (footprint "SOIC300-20")
      (description "Octal Buffer and Line Driver with 3-State Outputs")
      (fields
        (field (name "MANUFACTURER") "Texas Instruments")
        (field (name "MANUFACTURER PART NUMBER") "SN74HC541DWR")
        (field (name "SOURCE") "Digikey")
      )
      (libsource (lib "ScoreBoard") (part "IS/SN74HC541DWZ"))
    )
  )
  (nets
    (net (code "1") (name "/CLK6") (class "Default")
      (node (ref "U1") (pin "11") (pinfunction "LE_11") (pintype "input"))
    )
    (net (code "2") (name "/CLK7") (class "Default")
      (node (ref "U14") (pin "11") (pinfunction "LE_11") (pintype "input"))
    )
    (net (code "3") (name "/D0") (class "Default")
      (node (ref "U1") (pin "2") (pinfunction "D1_2") (pintype "input"))
      (node (ref "U10") (pin "18") (pinfunction "Y1_18") (pintype "tri_state"))
      (node (ref "U14") (pin "2") (pinfunction "D1_2") (pintype "input"))
      (node (ref "U18") (pin "18") (pinfunction "Y1_18") (pintype "tri_state"))
    )
    (net (code "4") (name "/D1") (class "Default")
      (node (ref "U1") (pin "3") (pinfunction "D2_3") (pintype "input"))
      (node (ref "U10") (pin "17") (pinfunction "Y2_17") (pintype "tri_state"))
      (node (ref "U14") (pin "3") (pinfunction "D2_3") (pintype "input"))
      (node (ref "U18") (pin "17") (pinfunction "Y2_17") (pintype "tri_state"))
    )
    (net (code "5") (name "/D2") (class "Default")
      (node (ref "U1") (pin "4") (pinfunction "D3_4") (pintype "input"))
      (node (ref "U10") (pin "16") (pinfunction "Y3_16") (pintype "tri_state"))
      (node (ref "U14") (pin "4") (pinfunction "D3_4") (pintype "input"))
      (node (ref "U18") (pin "16") (pinfunction "Y3_16") (pintype "tri_state"))
    )
    (net (code "6") (name "/D3") (class "Default")
      (node (ref "U1") (pin "5") (pinfunction "D4_5") (pintype "input"))
      (node (ref "U10") (pin "15") (pinfunction "Y4_15") (pintype "tri_state"))
      (node (ref "U14") (pin "5") (pinfunction "D4_5") (pintype "input"))
      (node (ref "U18") (pin "15") (pinfunction "Y4_15") (pintype "tri_state"))
    )
    (net (code "7") (name "/D4") (class "Default")
      (node (ref "U1") (pin "6") (pinfunction "D5_6") (pintype "input"))
      (node (ref "U10") (pin "14") (pinfunction "Y5_14") (pintype "tri_state"))
      (node (ref "U14") (pin "6") (pinfunction "D5_6") (pintype "input"))
      (node (ref "U18") (pin "14") (pinfunction "Y5_14") (pintype "tri_state"))
    )
    (net (code "8") (name "/D5") (class "Default")
      (node (ref "U1") (pin "7") (pinfunction "D6_7") (pintype "input"))
      (node (ref "U10") (pin "13") (pinfunction "Y6_13") (pintype "tri_state"))
      (node (ref "U14") (pin "7") (pinfunction "D6_7") (pintype "input"))
      (node (ref "U18") (pin "13") (pinfunction "Y6_13") (pintype "tri_state"))
    )
    (net (code "9") (name "/D6") (class "Default")
      (node (ref "U1") (pin "8") (pinfunction "D7_8") (pintype "input"))
      (node (ref "U10") (pin "12") (pinfunction "Y7_12") (pintype "tri_state"))
      (node (ref "U14") (pin "8") (pinfunction "D7_8") (pintype "input"))
      (node (ref "U18") (pin "12") (pinfunction "Y7_12") (pintype "tri_state"))
    )
    (net (code "10") (name "/D7") (class "Default")
      (node (ref "U1") (pin "9") (pinfunction "D8_9") (pintype "input"))
      (node (ref "U10") (pin "11") (pinfunction "Y8_11") (pintype "tri_state"))
      (node (ref "U14") (pin "9") (pinfunction "D8_9") (pintype "input"))
      (node (ref "U18") (pin "11") (pinfunction "Y8_11") (pintype "tri_state"))
    )
    (net (code "11") (name "/LAMP0") (class "Default")
      (node (ref "R6") (pin "1") (pinfunction "1_1") (pintype "passive"))
    )
    (net (code "12") (name "/LAMP1") (class "Default")
      (node (ref "R7") (pin "1") (pinfunction "1_1") (pintype "passive"))
    )
    (net (code "13") (name "/LAMP2") (class "Default")
      (node (ref "R8") (pin "1") (pinfunction "1_1") (pintype "passive"))
    )
    (net (code "14") (name "/LAMP3") (class "Default")
      (node (ref "R9") (pin "1") (pinfunction "1_1") (pintype "passive"))
    )
    (net (code "15") (name "/LAMP4") (class "Default")
      (node (ref "R10") (pin "1") (pinfunction "1_1") (pintype "passive"))
    )
    (net (code "16") (name "/LAMP5") (class "Default")
      (node (ref "R11") (pin "1") (pinfunction "1_1") (pintype "passive"))
    )
    (net (code "17") (name "/LAMP6") (class "Default")
      (node (ref "R12") (pin "1") (pinfunction "1_1") (pintype "passive"))
      (node (ref "U1") (pin "19") (pinfunction "Q1_19") (pintype "tri_state"))
    )
    (net (code "18") (name "/LAMP7") (class "Default")
      (node (ref "R13") (pin "1") (pinfunction "1_1") (pintype "passive"))
      (node (ref "U1") (pin "18") (pinfunction "Q2_18") (pintype "tri_state"))
    )
    (net (code "19") (name "/LAMP8") (class "Default")
      (node (ref "R14") (pin "1") (pinfunction "1_1") (pintype "passive"))
      (node (ref "U1") (pin "17") (pinfunction "Q3_17") (pintype "tri_state"))
    )
    (net (code "20") (name "/LAMP9") (class "Default")
      (node (ref "R15") (pin "1") (pinfunction "1_1") (pintype "passive"))
      (node (ref "U1") (pin "16") (pinfunction "Q4_16") (pintype "tri_state"))
    )
    (net (code "21") (name "/LAMP10") (class "Default")
      (node (ref "R62") (pin "1") (pinfunction "1_1") (pintype "passive"))
      (node (ref "U1") (pin "15") (pinfunction "Q5_15") (pintype "tri_state"))
    )
    (net (code "22") (name "/LAMP11") (class "Default")
      (node (ref "R63") (pin "1") (pinfunction "1_1") (pintype "passive"))
      (node (ref "U1") (pin "14") (pinfunction "Q6_14") (pintype "tri_state"))
    )
    (net (code "23") (name "/LAMP12") (class "Default")
      (node (ref "R64") (pin "1") (pinfunction "1_1") (pintype "passive"))
      (node (ref "U1") (pin "13") (pinfunction "Q7_13") (pintype "tri_state"))
    )
    (net (code "24") (name "/LAMP13") (class "Default")
      (node (ref "R65") (pin "1") (pinfunction "1_1") (pintype "passive"))
      (node (ref "U1") (pin "12") (pinfunction "Q8_12") (pintype "tri_state"))
    )
    (net (code "25") (name "/LAMP14") (class "Default")
      (node (ref "R66") (pin "1") (pinfunction "1_1") (pintype "passive"))
      (node (ref "U14") (pin "19") (pinfunction "Q1_19") (pintype "tri_state"))
    )
    (net (code "26") (name "/LAMP15") (class "Default")
      (node (ref "R69") (pin "1") (pinfunction "1_1") (pintype "passive"))
      (node (ref "U14") (pin "18") (pinfunction "Q2_18") (pintype "tri_state"))
    )
    (net (code "27") (name "/LAMP16") (class "Default")
      (node (ref "R70") (pin "1") (pinfunction "1_1") (pintype "passive"))
      (node (ref "U14") (pin "17") (pinfunction "Q3_17") (pintype "tri_state"))
    )
    (net (code "28") (name "/LAMP17") (class "Default")
      (node (ref "R71") (pin "1") (pinfunction "1_1") (pintype "passive"))
      (node (ref "U14") (pin "16") (pinfunction "Q4_16") (pintype "tri_state"))
    )
    (net (code "29") (name "/LAMP18") (class "Default")
      (node (ref "R72") (pin "1") (pinfunction "1_1") (pintype "passive"))
      (node (ref "U14") (pin "15") (pinfunction "Q5_15") (pintype "tri_state"))
    )
    (net (code "30") (name "/LAMP19") (class "Default")
      (node (ref "R73") (pin "1") (pinfunction "1_1") (pintype "passive"))
      (node (ref "U14") (pin "14") (pinfunction "Q6_14") (pintype "tri_state"))
    )
    (net (code "31") (name "/LAMP20") (class "Default")
      (node (ref "U14") (pin "13") (pinfunction "Q7_13") (pintype "tri_state"))
    )
    (net (code "32") (name "/LED_OE") (class "Default")
      (node (ref "U1") (pin "1") (pinfunction "~{OE}_1") (pintype "input"))
      (node (ref "U14") (pin "1") (pinfunction "~{OE}_1") (pintype "input"))
    )
    (net (code "33") (name "/SWITCH0") (class "Default")
      (node (ref "D3") (pin "2") (pinfunction "K_2") (pintype "passive"))
      (node (ref "R33") (pin "1") (pinfunction "1_1") (pintype "passive"))
      (node (ref "R34") (pin "1") (pinfunction "1_1") (pintype "passive"))
      (node (ref "U10") (pin "2") (pinfunction "A1_2") (pintype "input"))
    )
    (net (code "34") (name "/SWITCH1") (class "Default")
      (node (ref "D4") (pin "2") (pinfunction "K_2") (pintype "passive"))
      (node (ref "R35") (pin "1") (pinfunction "1_1") (pintype "passive"))
      (node (ref "R36") (pin "1") (pinfunction "1_1") (pintype "passive"))
      (node (ref "U10") (pin "3") (pinfunction "A2_3") (pintype "input"))
    )
    (net (code "35") (name "/SWITCH2") (class "Default")
      (node (ref "D5") (pin "2") (pinfunction "K_2") (pintype "passive"))
      (node (ref "R37") (pin "1") (pinfunction "1_1") (pintype "passive"))
      (node (ref "R38") (pin "1") (pinfunction "1_1") (pintype "passive"))
      (node (ref "U10") (pin "4") (pinfunction "A3_4") (pintype "input"))
    )
    (net (code "36") (name "/SWITCH3") (class "Default")
      (node (ref "D25") (pin "2") (pinfunction "K_2") (pintype "passive"))
      (node (ref "R39") (pin "1") (pinfunction "1_1") (pintype "passive"))
      (node (ref "R40") (pin "1") (pinfunction "1_1") (pintype "passive"))
      (node (ref "U10") (pin "5") (pinfunction "A4_5") (pintype "input"))
    )
    (net (code "37") (name "/SWITCH4") (class "Default")
      (node (ref "D8") (pin "2") (pinfunction "K_2") (pintype "passive"))
      (node (ref "R41") (pin "1") (pinfunction "1_1") (pintype "passive"))
      (node (ref "R42") (pin "1") (pinfunction "1_1") (pintype "passive"))
      (node (ref "U10") (pin "6") (pinfunction "A5_6") (pintype "input"))
    )
    (net (code "38") (name "/SWITCH5") (class "Default")
      (node (ref "D9") (pin "2") (pinfunction "K_2") (pintype "passive"))
      (node (ref "R43") (pin "1") (pinfunction "1_1") (pintype "passive"))
      (node (ref "R44") (pin "1") (pinfunction "1_1") (pintype "passive"))
      (node (ref "U10") (pin "7") (pinfunction "A6_7") (pintype "input"))
    )
    (net (code "39") (name "/SWITCH6") (class "Default")
      (node (ref "D10") (pin "2") (pinfunction "K_2") (pintype "passive"))
      (node (ref "R45") (pin "1") (pinfunction "1_1") (pintype "passive"))
      (node (ref "R46") (pin "1") (pinfunction "1_1") (pintype "passive"))
      (node (ref "U10") (pin "8") (pinfunction "A7_8") (pintype "input"))
    )
    (net (code "40") (name "/SWITCH7") (class "Default")
      (node (ref "D11") (pin "2") (pinfunction "K_2") (pintype "passive"))
      (node (ref "R47") (pin "1") (pinfunction "1_1") (pintype "passive"))
      (node (ref "R48") (pin "1") (pinfunction "1_1") (pintype "passive"))
      (node (ref "U10") (pin "9") (pinfunction "A8_9") (pintype "input"))
    )
    (net (code "41") (name "/SWITCH8") (class "Default")
      (node (ref "D6") (pin "2") (pinfunction "K_2") (pintype "passive"))
      (node (ref "R49") (pin "1") (pinfunction "1_1") (pintype "passive"))
      (node (ref "R50") (pin "1") (pinfunction "1_1") (pintype "passive"))
      (node (ref "U18") (pin "2") (pinfunction "A1_2") (pintype "input"))
    )
    (net (code "42") (name "/SWITCH9") (class "Default")
      (node (ref "D7") (pin "2") (pinfunction "K_2") (pintype "passive"))
      (node (ref "R51") (pin "1") (pinfunction "1_1") (pintype "passive"))
      (node (ref "R52") (pin "1") (pinfunction "1_1") (pintype "passive"))
      (node (ref "U18") (pin "3") (pinfunction "A2_3") (pintype "input"))
    )
    (net (code "43") (name "/SWITCH10") (class "Default")
      (node (ref "D15") (pin "2") (pinfunction "K_2") (pintype "passive"))
      (node (ref "R84") (pin "1") (pinfunction "1_1") (pintype "passive"))
      (node (ref "R85") (pin "1") (pinfunction "1_1") (pintype "passive"))
      (node (ref "U18") (pin "4") (pinfunction "A3_4") (pintype "input"))
    )
    (net (code "44") (name "/SWITCH11") (class "Default")
      (node (ref "D16") (pin "2") (pinfunction "K_2") (pintype "passive"))
      (node (ref "R86") (pin "1") (pinfunction "1_1") (pintype "passive"))
      (node (ref "R87") (pin "1") (pinfunction "1_1") (pintype "passive"))
      (node (ref "U18") (pin "5") (pinfunction "A4_5") (pintype "input"))
    )
    (net (code "45") (name "/SWITCH12") (class "Default")
      (node (ref "D17") (pin "2") (pinfunction "K_2") (pintype "passive"))
      (node (ref "R88") (pin "1") (pinfunction "1_1") (pintype "passive"))
      (node (ref "R89") (pin "1") (pinfunction "1_1") (pintype "passive"))
      (node (ref "U18") (pin "6") (pinfunction "A5_6") (pintype "input"))
    )
    (net (code "46") (name "/SWITCH13") (class "Default")
      (node (ref "D18") (pin "2") (pinfunction "K_2") (pintype "passive"))
      (node (ref "R90") (pin "1") (pinfunction "1_1") (pintype "passive"))
      (node (ref "R91") (pin "1") (pinfunction "1_1") (pintype "passive"))
      (node (ref "U18") (pin "7") (pinfunction "A6_7") (pintype "input"))
    )
    (net (code "47") (name "/SWITCH14") (class "Default")
      (node (ref "D19") (pin "2") (pinfunction "K_2") (pintype "passive"))
      (node (ref "R92") (pin "1") (pinfunction "1_1") (pintype "passive"))
      (node (ref "R93") (pin "1") (pinfunction "1_1") (pintype "passive"))
      (node (ref "U18") (pin "8") (pinfunction "A7_8") (pintype "input"))
    )
    (net (code "48") (name "/SWITCH15") (class "Default")
      (node (ref "D20") (pin "2") (pinfunction "K_2") (pintype "passive"))
      (node (ref "R94") (pin "1") (pinfunction "1_1") (pintype "passive"))
      (node (ref "R95") (pin "1") (pinfunction "1_1") (pintype "passive"))
      (node (ref "U18") (pin "9") (pinfunction "A8_9") (pintype "input"))
    )
    (net (code "49") (name "/SWITCH16") (class "Default")
      (node (ref "D21") (pin "2") (pinfunction "K_2") (pintype "passive"))
      (node (ref "R96") (pin "1") (pinfunction "1_1") (pintype "passive"))
      (node (ref "R97") (pin "1") (pinfunction "1_1") (pintype "passive"))
    )
    (net (code "50") (name "/SWITCH17") (class "Default")
      (node (ref "D22") (pin "2") (pinfunction "K_2") (pintype "passive"))
      (node (ref "R98") (pin "1") (pinfunction "1_1") (pintype "passive"))
      (node (ref "R99") (pin "1") (pinfunction "1_1") (pintype "passive"))
    )
    (net (code "51") (name "/SWITCH18") (class "Default")
      (node (ref "D23") (pin "2") (pinfunction "K_2") (pintype "passive"))
      (node (ref "R100") (pin "1") (pinfunction "1_1") (pintype "passive"))
      (node (ref "R101") (pin "1") (pinfunction "1_1") (pintype "passive"))
    )
    (net (code "52") (name "/SWITCH19") (class "Default")
      (node (ref "D24") (pin "2") (pinfunction "K_2") (pintype "passive"))
      (node (ref "R102") (pin "1") (pinfunction "1_1") (pintype "passive"))
      (node (ref "R103") (pin "1") (pinfunction "1_1") (pintype "passive"))
    )
    (net (code "53") (name "/SWITCHES0-7") (class "Default")
      (node (ref "R55") (pin "2") (pinfunction "2_2") (pintype "passive"))
      (node (ref "U10") (pin "1") (pinfunction "~{OE}1_1") (pintype "input"))
      (node (ref "U10") (pin "19") (pinfunction "~{OE}2_19") (pintype "input"))
    )
    (net (code "54") (name "/SWITCHES8-15") (class "Default")
      (node (ref "R104") (pin "2") (pinfunction "2_2") (pintype "passive"))
      (node (ref "U18") (pin "1") (pinfunction "~{OE}1_1") (pintype "input"))
      (node (ref "U18") (pin "19") (pinfunction "~{OE}2_19") (pintype "input"))
    )
    (net (code "55") (name "GND") (class "Default")
      (node (ref "C30") (pin "2") (pinfunction "2_2") (pintype "passive"))
      (node (ref "C37") (pin "2") (pinfunction "2_2") (pintype "passive"))
      (node (ref "C4") (pin "2") (pinfunction "2_2") (pintype "passive"))
      (node (ref "C46") (pin "2") (pinfunction "2_2") (pintype "passive"))
      (node (ref "D10") (pin "1") (pinfunction "A_1") (pintype "passive"))
      (node (ref "D11") (pin "1") (pinfunction "A_1") (pintype "passive"))
      (node (ref "D15") (pin "1") (pinfunction "A_1") (pintype "passive"))
      (node (ref "D16") (pin "1") (pinfunction "A_1") (pintype "passive"))
      (node (ref "D17") (pin "1") (pinfunction "A_1") (pintype "passive"))
      (node (ref "D18") (pin "1") (pinfunction "A_1") (pintype "passive"))
      (node (ref "D19") (pin "1") (pinfunction "A_1") (pintype "passive"))
      (node (ref "D20") (pin "1") (pinfunction "A_1") (pintype "passive"))
      (node (ref "D21") (pin "1") (pinfunction "A_1") (pintype "passive"))
      (node (ref "D22") (pin "1") (pinfunction "A_1") (pintype "passive"))
      (node (ref "D23") (pin "1") (pinfunction "A_1") (pintype "passive"))
      (node (ref "D24") (pin "1") (pinfunction "A_1") (pintype "passive"))
      (node (ref "D25") (pin "1") (pinfunction "A_1") (pintype "passive"))
      (node (ref "D3") (pin "1") (pinfunction "A_1") (pintype "passive"))
      (node (ref "D4") (pin "1") (pinfunction "A_1") (pintype "passive"))
      (node (ref "D5") (pin "1") (pinfunction "A_1") (pintype "passive"))
      (node (ref "D6") (pin "1") (pinfunction "A_1") (pintype "passive"))
      (node (ref "D7") (pin "1") (pinfunction "A_1") (pintype "passive"))
      (node (ref "D8") (pin "1") (pinfunction "A_1") (pintype "passive"))
      (node (ref "D9") (pin "1") (pinfunction "A_1") (pintype "passive"))
      (node (ref "Q1") (pin "3") (pinfunction "S_3") (pintype "passive"))
      (node (ref "Q10") (pin "3") (pinfunction "S_3") (pintype "passive"))
      (node (ref "Q11") (pin "3") (pinfunction "S_3") (pintype "passive"))
      (node (ref "Q12") (pin "3") (pinfunction "S_3") (pintype "passive"))
      (node (ref "Q13") (pin "3") (pinfunction "S_3") (pintype "passive"))
      (node (ref "Q14") (pin "3") (pinfunction "S_3") (pintype "passive"))
      (node (ref "Q15") (pin "3") (pinfunction "S_3") (pintype "passive"))
      (node (ref "Q16") (pin "3") (pinfunction "S_3") (pintype "passive"))
      (node (ref "Q17") (pin "3") (pinfunction "S_3") (pintype "passive"))
      (node (ref "Q18") (pin "3") (pinfunction "S_3") (pintype "passive"))
      (node (ref "Q19") (pin "3") (pinfunction "S_3") (pintype "passive"))
      (node (ref "Q2") (pin "3") (pinfunction "S_3") (pintype "passive"))
      (node (ref "Q20") (pin "3") (pinfunction "S_3") (pintype "passive"))
      (node (ref "Q3") (pin "3") (pinfunction "S_3") (pintype "passive"))
      (node (ref "Q4") (pin "3") (pinfunction "S_3") (pintype "passive"))
      (node (ref "Q5") (pin "3") (pinfunction "S_3") (pintype "passive"))
      (node (ref "Q6") (pin "3") (pinfunction "S_3") (pintype "passive"))
      (node (ref "Q7") (pin "3") (pinfunction "S_3") (pintype "passive"))
      (node (ref "Q8") (pin "3") (pinfunction "S_3") (pintype "passive"))
      (node (ref "Q9") (pin "3") (pinfunction "S_3") (pintype "passive"))
      (node (ref "R101") (pin "2") (pinfunction "2_2") (pintype "passive"))
      (node (ref "R103") (pin "2") (pinfunction "2_2") (pintype "passive"))
      (node (ref "R34") (pin "2") (pinfunction "2_2") (pintype "passive"))
      (node (ref "R36") (pin "2") (pinfunction "2_2") (pintype "passive"))
      (node (ref "R38") (pin "2") (pinfunction "2_2") (pintype "passive"))
      (node (ref "R40") (pin "2") (pinfunction "2_2") (pintype "passive"))
      (node (ref "R42") (pin "2") (pinfunction "2_2") (pintype "passive"))
      (node (ref "R44") (pin "2") (pinfunction "2_2") (pintype "passive"))
      (node (ref "R46") (pin "2") (pinfunction "2_2") (pintype "passive"))
      (node (ref "R48") (pin "2") (pinfunction "2_2") (pintype "passive"))
      (node (ref "R50") (pin "2") (pinfunction "2_2") (pintype "passive"))
      (node (ref "R52") (pin "2") (pinfunction "2_2") (pintype "passive"))
      (node (ref "R85") (pin "2") (pinfunction "2_2") (pintype "passive"))
      (node (ref "R87") (pin "2") (pinfunction "2_2") (pintype "passive"))
      (node (ref "R89") (pin "2") (pinfunction "2_2") (pintype "passive"))
      (node (ref "R91") (pin "2") (pinfunction "2_2") (pintype "passive"))
      (node (ref "R93") (pin "2") (pinfunction "2_2") (pintype "passive"))
      (node (ref "R95") (pin "2") (pinfunction "2_2") (pintype "passive"))
      (node (ref "R97") (pin "2") (pinfunction "2_2") (pintype "passive"))
      (node (ref "R99") (pin "2") (pinfunction "2_2") (pintype "passive"))
      (node (ref "U1") (pin "10") (pinfunction "GND_10") (pintype "power_in"))
      (node (ref "U10") (pin "10") (pinfunction "GND_10") (pintype "power_in"))
      (node (ref "U14") (pin "10") (pinfunction "GND_10") (pintype "power_in"))
      (node (ref "U18") (pin "10") (pinfunction "GND_10") (pintype "power_in"))
    )
    (net (code "56") (name "Net-(J11-Pad1)") (class "Default")
      (node (ref "J11") (pin "1") (pinfunction "1_1") (pintype "passive"))
      (node (ref "R33") (pin "2") (pinfunction "2_2") (pintype "passive"))
    )
    (net (code "57") (name "Net-(J11-Pad2)") (class "Default")
      (node (ref "J11") (pin "2") (pinfunction "2_2") (pintype "passive"))
      (node (ref "R35") (pin "2") (pinfunction "2_2") (pintype "passive"))
    )
    (net (code "58") (name "Net-(J11-Pad3)") (class "Default")
      (node (ref "J11") (pin "3") (pinfunction "3_3") (pintype "passive"))
      (node (ref "R37") (pin "2") (pinfunction "2_2") (pintype "passive"))
    )
    (net (code "59") (name "Net-(J11-Pad4)") (class "Default")
      (node (ref "J11") (pin "4") (pinfunction "4_4") (pintype "passive"))
      (node (ref "R39") (pin "2") (pinfunction "2_2") (pintype "passive"))
    )
    (net (code "60") (name "Net-(J11-Pad5)") (class "Default")
      (node (ref "J11") (pin "5") (pinfunction "5_5") (pintype "passive"))
      (node (ref "R41") (pin "2") (pinfunction "2_2") (pintype "passive"))
    )
    (net (code "61") (name "Net-(J12-Pad1)") (class "Default")
      (node (ref "J12") (pin "1") (pinfunction "1_1") (pintype "passive"))
      (node (ref "R43") (pin "2") (pinfunction "2_2") (pintype "passive"))
    )
    (net (code "62") (name "Net-(J12-Pad2)") (class "Default")
      (node (ref "J12") (pin "2") (pinfunction "2_2") (pintype "passive"))
      (node (ref "R45") (pin "2") (pinfunction "2_2") (pintype "passive"))
    )
    (net (code "63") (name "Net-(J12-Pad3)") (class "Default")
      (node (ref "J12") (pin "3") (pinfunction "3_3") (pintype "passive"))
      (node (ref "R47") (pin "2") (pinfunction "2_2") (pintype "passive"))
    )
    (net (code "64") (name "Net-(J12-Pad4)") (class "Default")
      (node (ref "J12") (pin "4") (pinfunction "4_4") (pintype "passive"))
      (node (ref "R49") (pin "2") (pinfunction "2_2") (pintype "passive"))
    )
    (net (code "65") (name "Net-(J12-Pad5)") (class "Default")
      (node (ref "J12") (pin "5") (pinfunction "5_5") (pintype "passive"))
      (node (ref "R51") (pin "2") (pinfunction "2_2") (pintype "passive"))
    )
    (net (code "66") (name "Net-(J16-Pad1)") (class "Default")
      (node (ref "J16") (pin "1") (pinfunction "1_1") (pintype "passive"))
      (node (ref "R84") (pin "2") (pinfunction "2_2") (pintype "passive"))
    )
    (net (code "67") (name "Net-(J16-Pad2)") (class "Default")
      (node (ref "J16") (pin "2") (pinfunction "2_2") (pintype "passive"))
      (node (ref "R86") (pin "2") (pinfunction "2_2") (pintype "passive"))
    )
    (net (code "68") (name "Net-(J16-Pad3)") (class "Default")
      (node (ref "J16") (pin "3") (pinfunction "3_3") (pintype "passive"))
      (node (ref "R88") (pin "2") (pinfunction "2_2") (pintype "passive"))
    )
    (net (code "69") (name "Net-(J16-Pad4)") (class "Default")
      (node (ref "J16") (pin "4") (pinfunction "4_4") (pintype "passive"))
      (node (ref "R90") (pin "2") (pinfunction "2_2") (pintype "passive"))
    )
    (net (code "70") (name "Net-(J16-Pad5)") (class "Default")
      (node (ref "J16") (pin "5") (pinfunction "5_5") (pintype "passive"))
      (node (ref "R92") (pin "2") (pinfunction "2_2") (pintype "passive"))
    )
    (net (code "71") (name "Net-(J17-Pad1)") (class "Default")
      (node (ref "J17") (pin "1") (pinfunction "1_1") (pintype "passive"))
      (node (ref "R94") (pin "2") (pinfunction "2_2") (pintype "passive"))
    )
    (net (code "72") (name "Net-(J17-Pad2)") (class "Default")
      (node (ref "J17") (pin "2") (pinfunction "2_2") (pintype "passive"))
      (node (ref "R96") (pin "2") (pinfunction "2_2") (pintype "passive"))
    )
    (net (code "73") (name "Net-(J17-Pad3)") (class "Default")
      (node (ref "J17") (pin "3") (pinfunction "3_3") (pintype "passive"))
      (node (ref "R98") (pin "2") (pinfunction "2_2") (pintype "passive"))
    )
    (net (code "74") (name "Net-(J17-Pad4)") (class "Default")
      (node (ref "J17") (pin "4") (pinfunction "4_4") (pintype "passive"))
      (node (ref "R100") (pin "2") (pinfunction "2_2") (pintype "passive"))
    )
    (net (code "75") (name "Net-(J17-Pad5)") (class "Default")
      (node (ref "J17") (pin "5") (pinfunction "5_5") (pintype "passive"))
      (node (ref "R102") (pin "2") (pinfunction "2_2") (pintype "passive"))
    )
    (net (code "76") (name "Net-(Q1-D)") (class "Default")
      (node (ref "J11") (pin "12") (pinfunction "12_12") (pintype "passive"))
      (node (ref "Q1") (pin "2") (pinfunction "D_2") (pintype "passive"))
    )
    (net (code "77") (name "Net-(Q1-G)") (class "Default")
      (node (ref "Q1") (pin "1") (pinfunction "G_1") (pintype "passive"))
      (node (ref "R6") (pin "2") (pinfunction "2_2") (pintype "passive"))
    )
    (net (code "78") (name "Net-(Q2-D)") (class "Default")
      (node (ref "J11") (pin "11") (pinfunction "11_11") (pintype "passive"))
      (node (ref "Q2") (pin "2") (pinfunction "D_2") (pintype "passive"))
    )
    (net (code "79") (name "Net-(Q2-G)") (class "Default")
      (node (ref "Q2") (pin "1") (pinfunction "G_1") (pintype "passive"))
      (node (ref "R7") (pin "2") (pinfunction "2_2") (pintype "passive"))
    )
    (net (code "80") (name "Net-(Q3-D)") (class "Default")
      (node (ref "J11") (pin "10") (pinfunction "10_10") (pintype "passive"))
      (node (ref "Q3") (pin "2") (pinfunction "D_2") (pintype "passive"))
    )
    (net (code "81") (name "Net-(Q3-G)") (class "Default")
      (node (ref "Q3") (pin "1") (pinfunction "G_1") (pintype "passive"))
      (node (ref "R8") (pin "2") (pinfunction "2_2") (pintype "passive"))
    )
    (net (code "82") (name "Net-(Q4-D)") (class "Default")
      (node (ref "J11") (pin "9") (pinfunction "9_9") (pintype "passive"))
      (node (ref "Q4") (pin "2") (pinfunction "D_2") (pintype "passive"))
    )
    (net (code "83") (name "Net-(Q4-G)") (class "Default")
      (node (ref "Q4") (pin "1") (pinfunction "G_1") (pintype "passive"))
      (node (ref "R9") (pin "2") (pinfunction "2_2") (pintype "passive"))
    )
    (net (code "84") (name "Net-(Q5-D)") (class "Default")
      (node (ref "J11") (pin "8") (pinfunction "8_8") (pintype "passive"))
      (node (ref "Q5") (pin "2") (pinfunction "D_2") (pintype "passive"))
    )
    (net (code "85") (name "Net-(Q5-G)") (class "Default")
      (node (ref "Q5") (pin "1") (pinfunction "G_1") (pintype "passive"))
      (node (ref "R10") (pin "2") (pinfunction "2_2") (pintype "passive"))
    )
    (net (code "86") (name "Net-(Q6-D)") (class "Default")
      (node (ref "J12") (pin "12") (pinfunction "12_12") (pintype "passive"))
      (node (ref "Q6") (pin "2") (pinfunction "D_2") (pintype "passive"))
    )
    (net (code "87") (name "Net-(Q6-G)") (class "Default")
      (node (ref "Q6") (pin "1") (pinfunction "G_1") (pintype "passive"))
      (node (ref "R11") (pin "2") (pinfunction "2_2") (pintype "passive"))
    )
    (net (code "88") (name "Net-(Q7-D)") (class "Default")
      (node (ref "J12") (pin "11") (pinfunction "11_11") (pintype "passive"))
      (node (ref "Q7") (pin "2") (pinfunction "D_2") (pintype "passive"))
    )
    (net (code "89") (name "Net-(Q7-G)") (class "Default")
      (node (ref "Q7") (pin "1") (pinfunction "G_1") (pintype "passive"))
      (node (ref "R12") (pin "2") (pinfunction "2_2") (pintype "passive"))
    )
    (net (code "90") (name "Net-(Q8-D)") (class "Default")
      (node (ref "J12") (pin "10") (pinfunction "10_10") (pintype "passive"))
      (node (ref "Q8") (pin "2") (pinfunction "D_2") (pintype "passive"))
    )
    (net (code "91") (name "Net-(Q8-G)") (class "Default")
      (node (ref "Q8") (pin "1") (pinfunction "G_1") (pintype "passive"))
      (node (ref "R13") (pin "2") (pinfunction "2_2") (pintype "passive"))
    )
    (net (code "92") (name "Net-(Q9-D)") (class "Default")
      (node (ref "J12") (pin "9") (pinfunction "9_9") (pintype "passive"))
      (node (ref "Q9") (pin "2") (pinfunction "D_2") (pintype "passive"))
    )
    (net (code "93") (name "Net-(Q9-G)") (class "Default")
      (node (ref "Q9") (pin "1") (pinfunction "G_1") (pintype "passive"))
      (node (ref "R14") (pin "2") (pinfunction "2_2") (pintype "passive"))
    )
    (net (code "94") (name "Net-(Q10-D)") (class "Default")
      (node (ref "J12") (pin "8") (pinfunction "8_8") (pintype "passive"))
      (node (ref "Q10") (pin "2") (pinfunction "D_2") (pintype "passive"))
    )
    (net (code "95") (name "Net-(Q10-G)") (class "Default")
      (node (ref "Q10") (pin "1") (pinfunction "G_1") (pintype "passive"))
      (node (ref "R15") (pin "2") (pinfunction "2_2") (pintype "passive"))
    )
    (net (code "96") (name "Net-(Q11-D)") (class "Default")
      (node (ref "J16") (pin "12") (pinfunction "12_12") (pintype "passive"))
      (node (ref "Q11") (pin "2") (pinfunction "D_2") (pintype "passive"))
    )
    (net (code "97") (name "Net-(Q11-G)") (class "Default")
      (node (ref "Q11") (pin "1") (pinfunction "G_1") (pintype "passive"))
      (node (ref "R62") (pin "2") (pinfunction "2_2") (pintype "passive"))
    )
    (net (code "98") (name "Net-(Q12-D)") (class "Default")
      (node (ref "J16") (pin "11") (pinfunction "11_11") (pintype "passive"))
      (node (ref "Q12") (pin "2") (pinfunction "D_2") (pintype "passive"))
    )
    (net (code "99") (name "Net-(Q12-G)") (class "Default")
      (node (ref "Q12") (pin "1") (pinfunction "G_1") (pintype "passive"))
      (node (ref "R63") (pin "2") (pinfunction "2_2") (pintype "passive"))
    )
    (net (code "100") (name "Net-(Q13-D)") (class "Default")
      (node (ref "J16") (pin "10") (pinfunction "10_10") (pintype "passive"))
      (node (ref "Q13") (pin "2") (pinfunction "D_2") (pintype "passive"))
    )
    (net (code "101") (name "Net-(Q13-G)") (class "Default")
      (node (ref "Q13") (pin "1") (pinfunction "G_1") (pintype "passive"))
      (node (ref "R64") (pin "2") (pinfunction "2_2") (pintype "passive"))
    )
    (net (code "102") (name "Net-(Q14-D)") (class "Default")
      (node (ref "J16") (pin "9") (pinfunction "9_9") (pintype "passive"))
      (node (ref "Q14") (pin "2") (pinfunction "D_2") (pintype "passive"))
    )
    (net (code "103") (name "Net-(Q14-G)") (class "Default")
      (node (ref "Q14") (pin "1") (pinfunction "G_1") (pintype "passive"))
      (node (ref "R65") (pin "2") (pinfunction "2_2") (pintype "passive"))
    )
    (net (code "104") (name "Net-(Q15-D)") (class "Default")
      (node (ref "J16") (pin "8") (pinfunction "8_8") (pintype "passive"))
      (node (ref "Q15") (pin "2") (pinfunction "D_2") (pintype "passive"))
    )
    (net (code "105") (name "Net-(Q15-G)") (class "Default")
      (node (ref "Q15") (pin "1") (pinfunction "G_1") (pintype "passive"))
      (node (ref "R66") (pin "2") (pinfunction "2_2") (pintype "passive"))
    )
    (net (code "106") (name "Net-(Q16-D)") (class "Default")
      (node (ref "J17") (pin "12") (pinfunction "12_12") (pintype "passive"))
      (node (ref "Q16") (pin "2") (pinfunction "D_2") (pintype "passive"))
    )
    (net (code "107") (name "Net-(Q16-G)") (class "Default")
      (node (ref "Q16") (pin "1") (pinfunction "G_1") (pintype "passive"))
      (node (ref "R69") (pin "2") (pinfunction "2_2") (pintype "passive"))
    )
    (net (code "108") (name "Net-(Q17-D)") (class "Default")
      (node (ref "J17") (pin "11") (pinfunction "11_11") (pintype "passive"))
      (node (ref "Q17") (pin "2") (pinfunction "D_2") (pintype "passive"))
    )
    (net (code "109") (name "Net-(Q17-G)") (class "Default")
      (node (ref "Q17") (pin "1") (pinfunction "G_1") (pintype "passive"))
      (node (ref "R70") (pin "2") (pinfunction "2_2") (pintype "passive"))
    )
    (net (code "110") (name "Net-(Q18-D)") (class "Default")
      (node (ref "J17") (pin "10") (pinfunction "10_10") (pintype "passive"))
      (node (ref "Q18") (pin "2") (pinfunction "D_2") (pintype "passive"))
    )
    (net (code "111") (name "Net-(Q18-G)") (class "Default")
      (node (ref "Q18") (pin "1") (pinfunction "G_1") (pintype "passive"))
      (node (ref "R71") (pin "2") (pinfunction "2_2") (pintype "passive"))
    )
    (net (code "112") (name "Net-(Q19-D)") (class "Default")
      (node (ref "J17") (pin "9") (pinfunction "9_9") (pintype "passive"))
      (node (ref "Q19") (pin "2") (pinfunction "D_2") (pintype "passive"))
    )
    (net (code "113") (name "Net-(Q19-G)") (class "Default")
      (node (ref "Q19") (pin "1") (pinfunction "G_1") (pintype "passive"))
      (node (ref "R72") (pin "2") (pinfunction "2_2") (pintype "passive"))
    )
    (net (code "114") (name "Net-(Q20-D)") (class "Default")
      (node (ref "J17") (pin "8") (pinfunction "8_8") (pintype "passive"))
      (node (ref "Q20") (pin "2") (pinfunction "D_2") (pintype "passive"))
    )
    (net (code "115") (name "Net-(Q20-G)") (class "Default")
      (node (ref "Q20") (pin "1") (pinfunction "G_1") (pintype "passive"))
      (node (ref "R73") (pin "2") (pinfunction "2_2") (pintype "passive"))
    )
    (net (code "116") (name "VCC") (class "Default")
      (node (ref "C30") (pin "1") (pinfunction "1_1") (pintype "passive"))
      (node (ref "C37") (pin "1") (pinfunction "1_1") (pintype "passive"))
      (node (ref "C4") (pin "1") (pinfunction "1_1") (pintype "passive"))
      (node (ref "C46") (pin "1") (pinfunction "1_1") (pintype "passive"))
      (node (ref "R104") (pin "1") (pinfunction "1_1") (pintype "passive"))
      (node (ref "R55") (pin "1") (pinfunction "1_1") (pintype "passive"))
      (node (ref "U1") (pin "20") (pinfunction "VCC_20") (pintype "power_in"))
      (node (ref "U10") (pin "20") (pinfunction "VCC_20") (pintype "power_in"))
      (node (ref "U14") (pin "20") (pinfunction "VCC_20") (pintype "power_in"))
      (node (ref "U18") (pin "20") (pinfunction "VCC_20") (pintype "power_in"))
    )
    (net (code "117") (name "Vbat") (class "Default")
      (node (ref "J11") (pin "6") (pinfunction "6_6") (pintype "passive"))
      (node (ref "J11") (pin "7") (pinfunction "7_7") (pintype "passive"))
      (node (ref "J12") (pin "6") (pinfunction "6_6") (pintype "passive"))
      (node (ref "J12") (pin "7") (pinfunction "7_7") (pintype "passive"))
      (node (ref "J16") (pin "6") (pinfunction "6_6") (pintype "passive"))
      (node (ref "J16") (pin "7") (pinfunction "7_7") (pintype "passive"))
      (node (ref "J17") (pin "6") (pinfunction "6_6") (pintype "passive"))
      (node (ref "J17") (pin "7") (pinfunction "7_7") (pintype "passive"))
    )
    (net (code "118") (name "unconnected-(U14-Q8-Pad12)") (class "Default")
      (node (ref "U14") (pin "12") (pinfunction "Q8_12") (pintype "tri_state"))
    )
  )
)
